# Placa_Base.net
KiCad netlist of a schematic drawn in Altium Designer
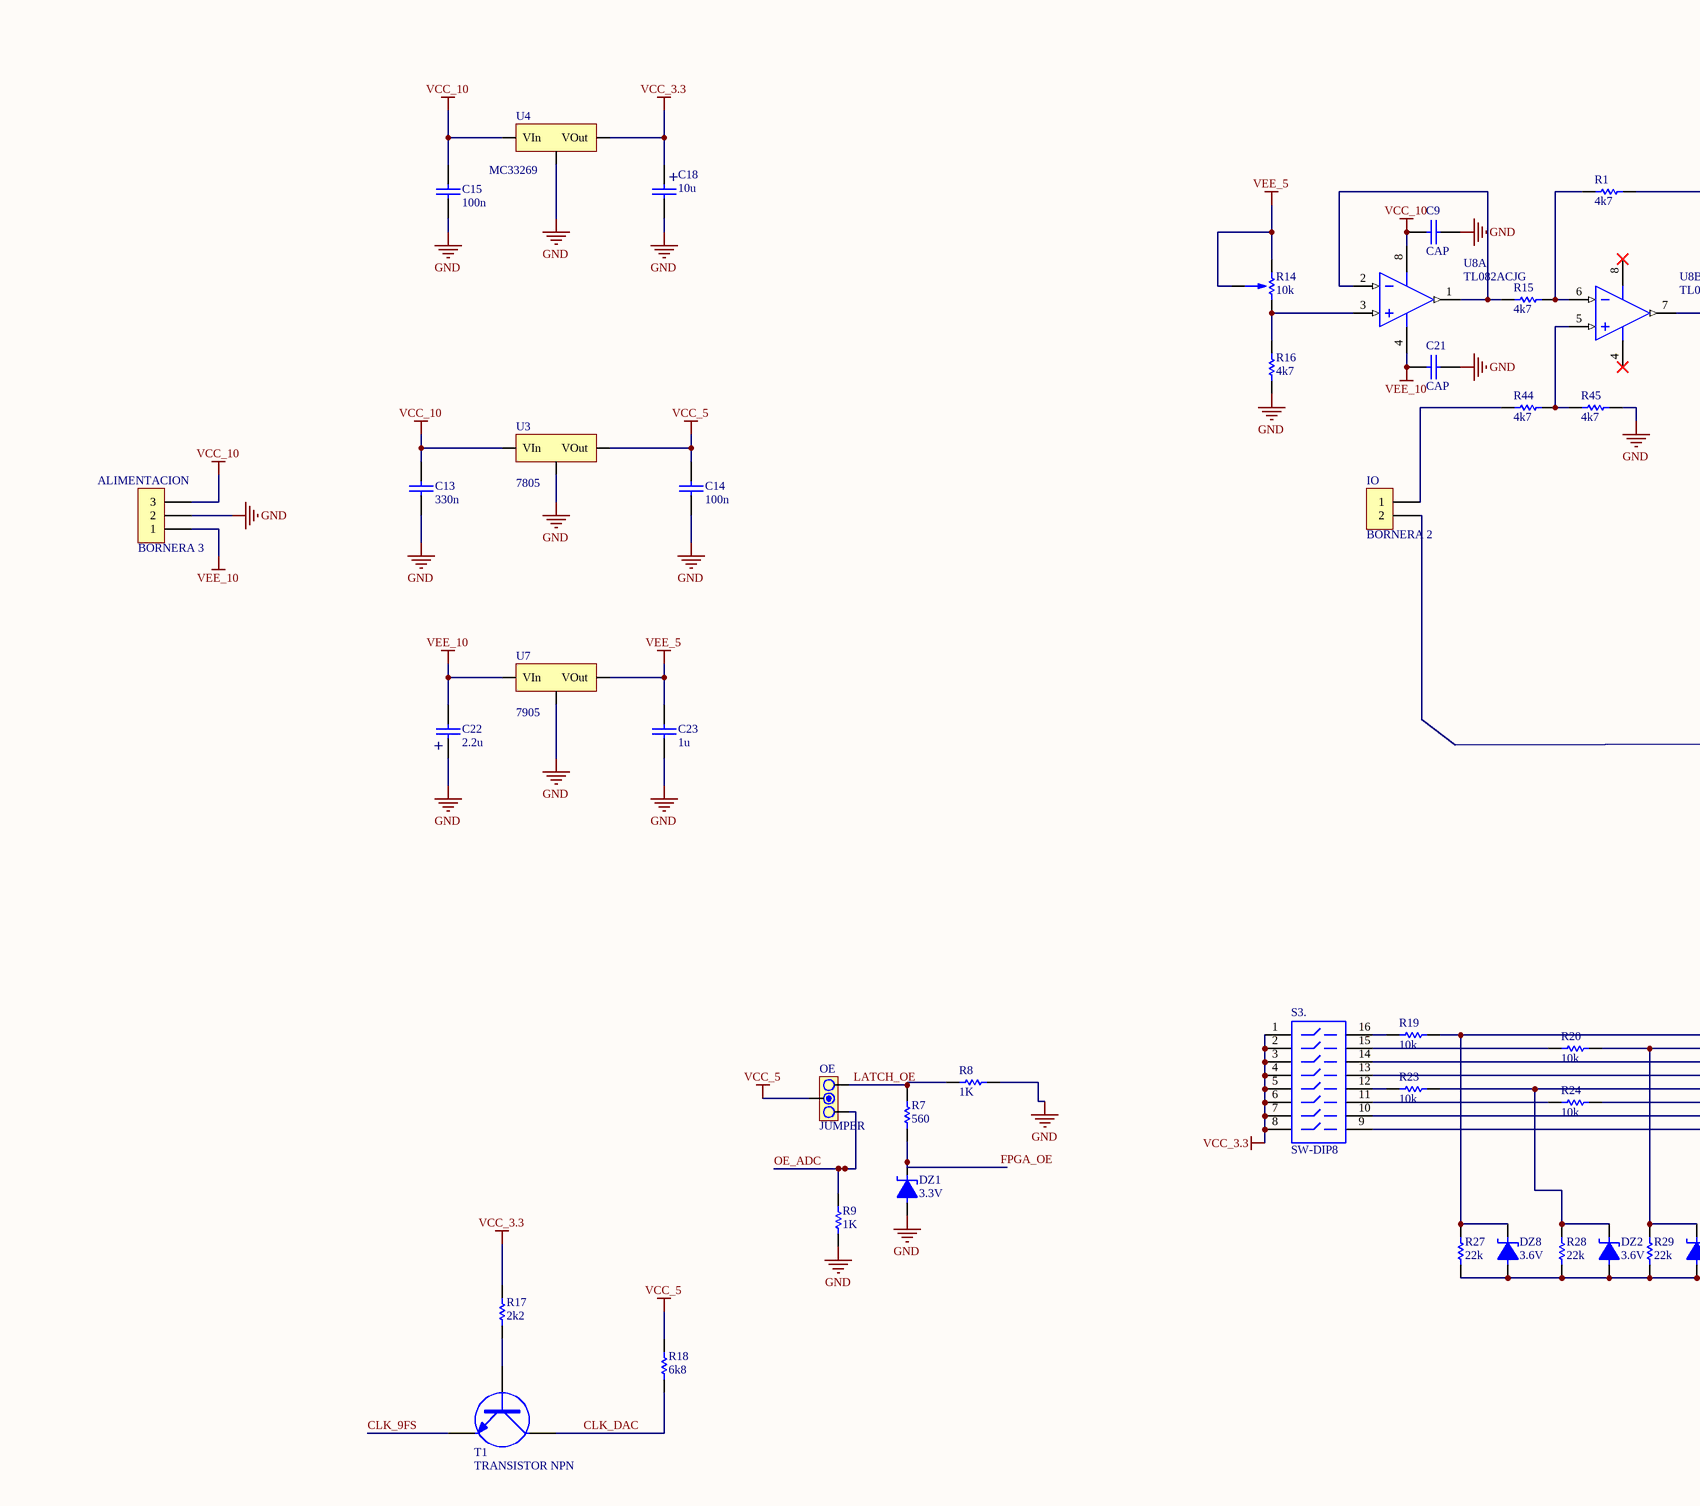
[diagram p0: Placa_Base.SchDoc, top left]
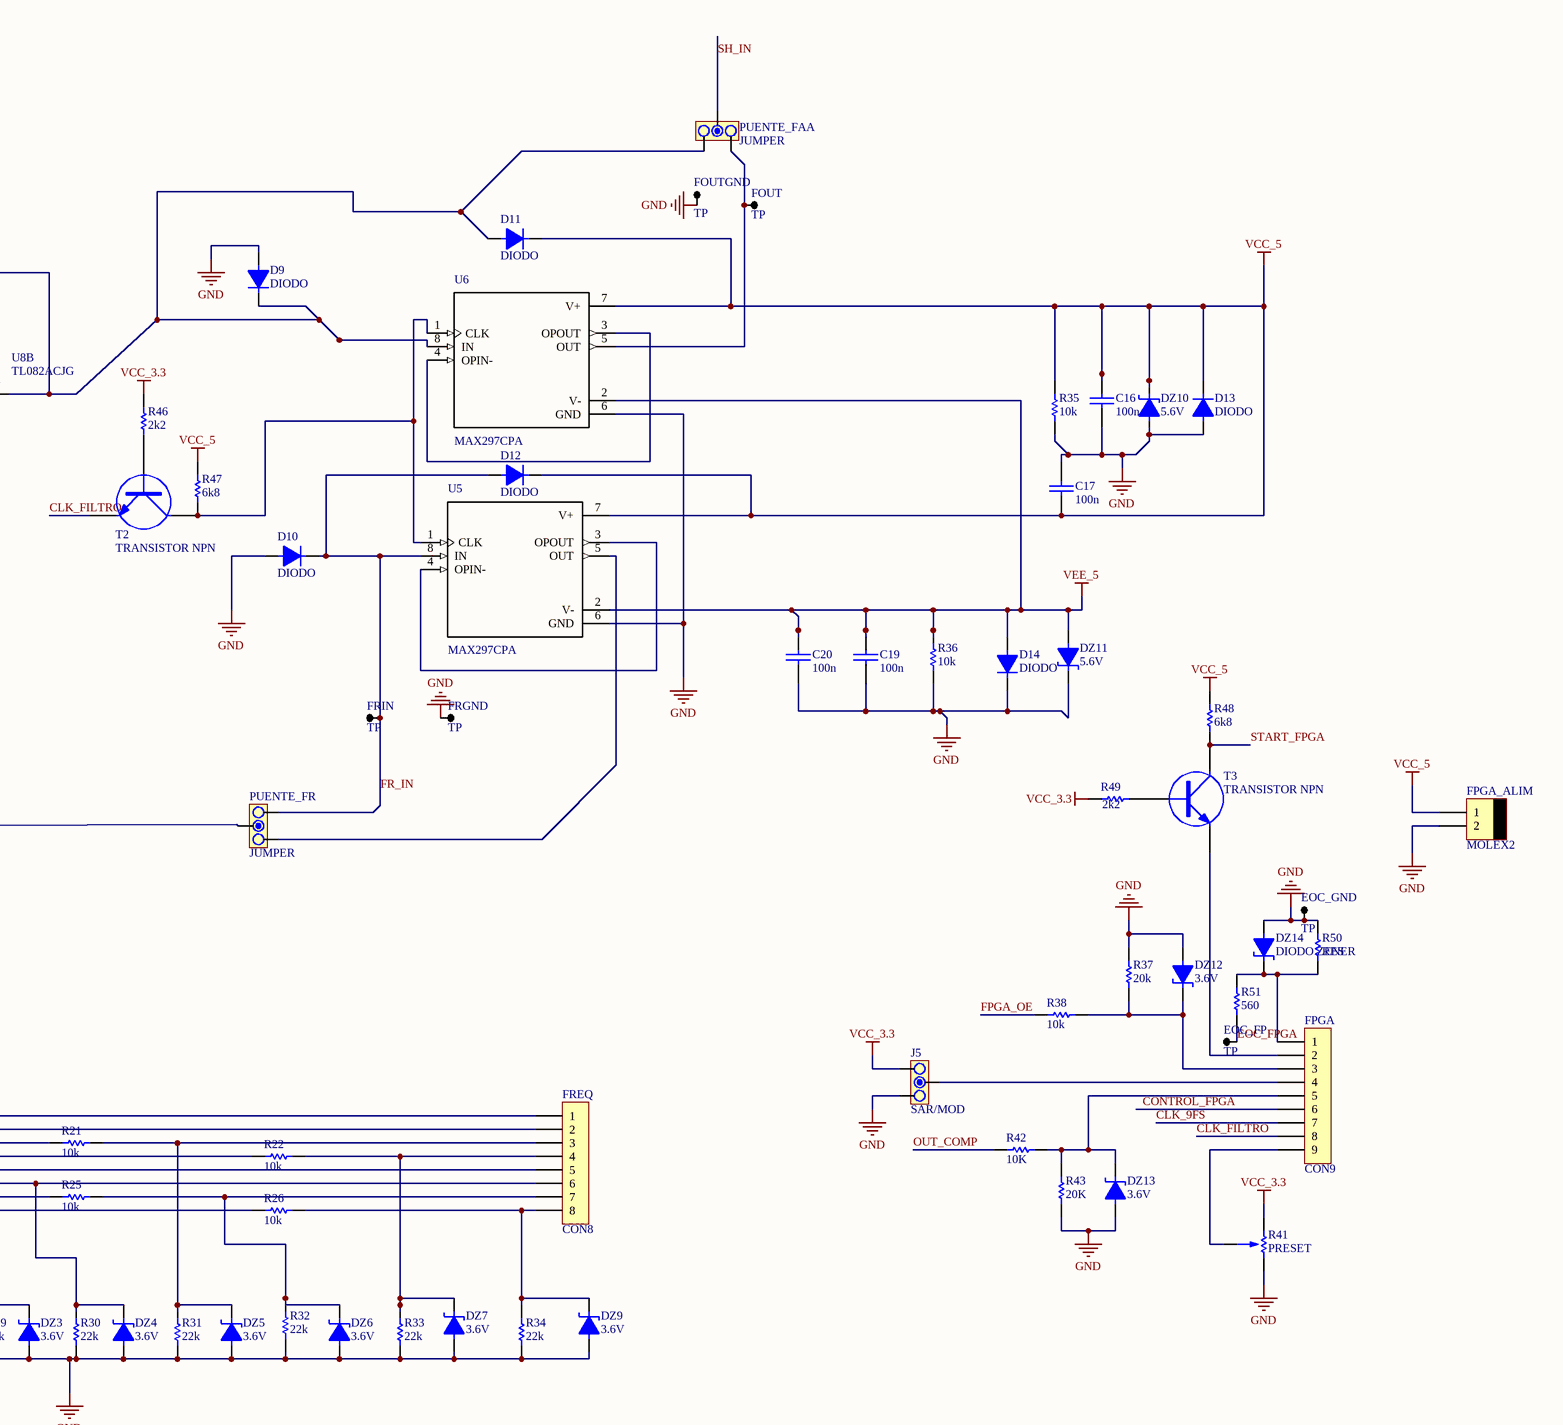
[diagram p1: Placa_Base.SchDoc, top right]
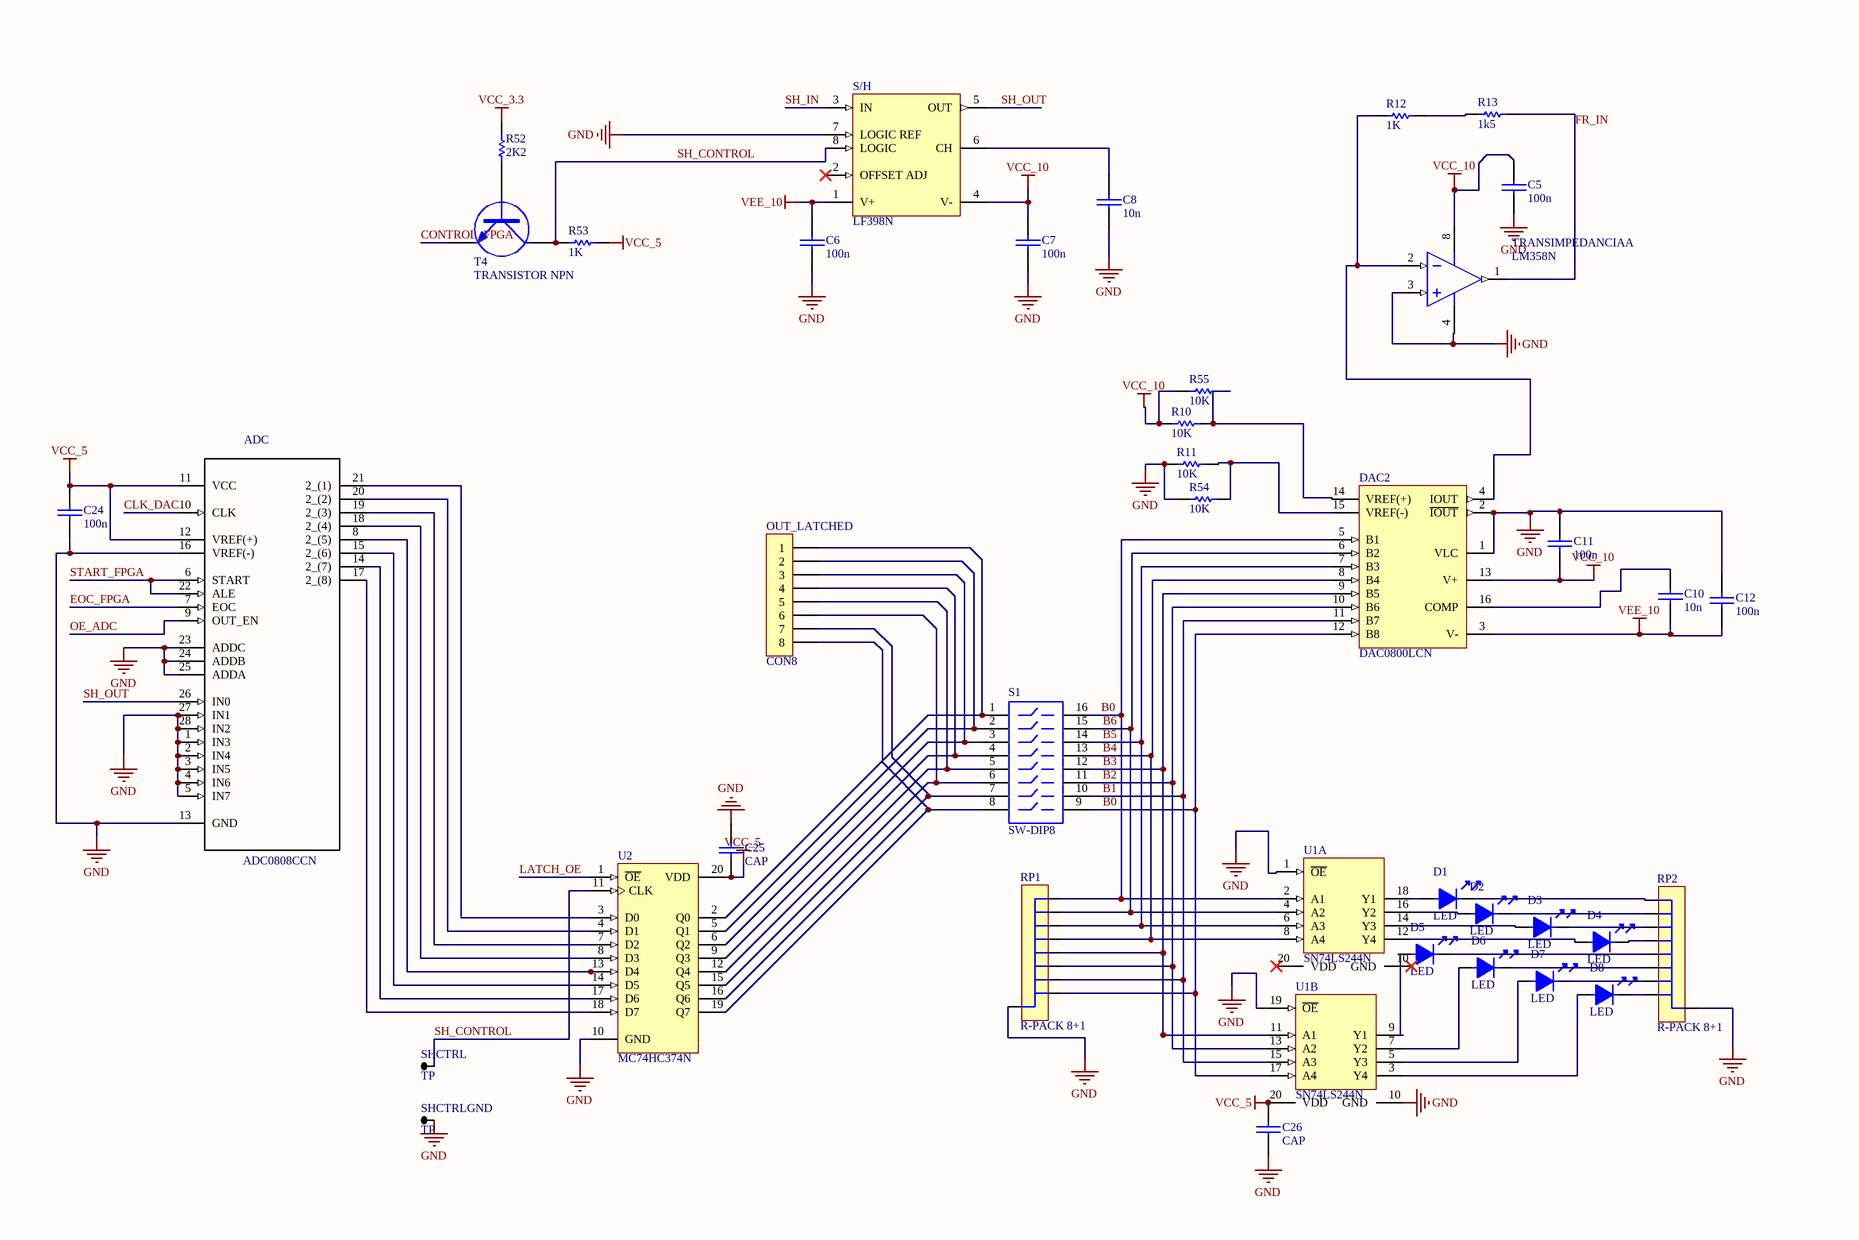
[diagram p2: Placa_Base.SchDoc, bottom left]
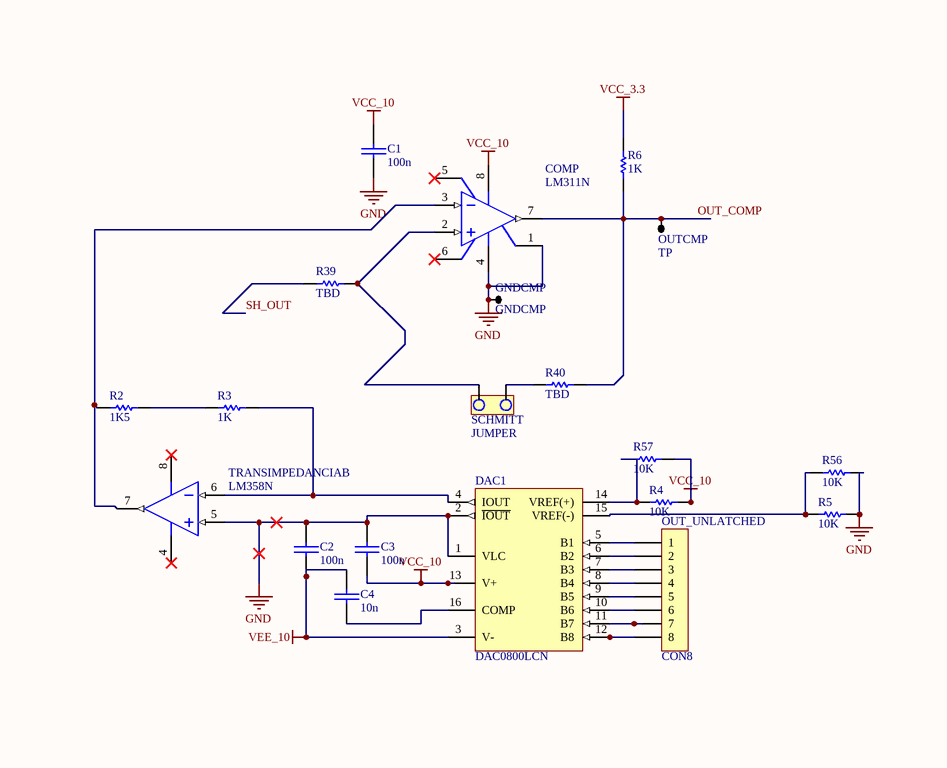
[diagram p3: Placa_Base.SchDoc, bottom right]

(export (version "E")
  (design (tool "Eeschema 10.0.6"))
  (components
    (comp (ref "ADC")
      (value "ADC0808CCN")
      (footprint "DIP28")
      (description "28 pin 8-bit Microprocessor Compatible A/D Converters With 8-Channel Multiplexer 13 per tube")
      (fields (field (name "MF") "Texas Instruments"))
      (libsource (lib "ADC0808CCN") (part "ADC0808CCN"))
    )
    (comp (ref "ALIMENTACION")
      (value "BORNERA 3")
      (footprint "BORNERA3")
      (libsource (lib "LIBEBAL") (part "BORNERA 3"))
    )
    (comp (ref "C1") (value "100n") (footprint "CAP200") (libsource (lib "LIBEBAL") (part "CAP")))
    (comp (ref "C2") (value "100n") (footprint "CAP200") (libsource (lib "LIBEBAL") (part "CAP")))
    (comp (ref "C3") (value "100n") (footprint "CAP200") (libsource (lib "LIBEBAL") (part "CAP")))
    (comp (ref "C4") (value "10n") (footprint "CAP200") (libsource (lib "LIBEBAL") (part "CAP")))
    (comp (ref "C5") (value "100n") (footprint "CAP200") (libsource (lib "LIBEBAL") (part "CAP")))
    (comp (ref "C6") (value "100n") (footprint "CAP200") (libsource (lib "LIBEBAL") (part "CAP")))
    (comp (ref "C7") (value "100n") (footprint "CAP200") (libsource (lib "LIBEBAL") (part "CAP")))
    (comp (ref "C8") (value "10n") (footprint "CAP200") (libsource (lib "LIBEBAL") (part "CAP")))
    (comp (ref "C9") (value "CAP") (footprint "CAP200") (libsource (lib "LIBEBAL") (part "CAP")))
    (comp (ref "C10") (value "10n") (footprint "CAP200") (libsource (lib "LIBEBAL") (part "CAP")))
    (comp (ref "C11") (value "100n") (footprint "CAP200") (libsource (lib "LIBEBAL") (part "CAP")))
    (comp (ref "C12") (value "100n") (footprint "CAP200") (libsource (lib "LIBEBAL") (part "CAP")))
    (comp (ref "C13") (value "330n") (footprint "CAP200") (libsource (lib "LIBEBAL") (part "CAP")))
    (comp (ref "C14") (value "100n") (footprint "CAP200") (libsource (lib "LIBEBAL") (part "CAP")))
    (comp (ref "C15") (value "100n") (footprint "CAP200") (libsource (lib "LIBEBAL") (part "CAP")))
    (comp (ref "C16") (value "100n") (footprint "CAP200") (libsource (lib "LIBEBAL") (part "CAP")))
    (comp (ref "C17") (value "100n") (footprint "CAP200") (libsource (lib "LIBEBAL") (part "CAP")))
    (comp (ref "C18") (value "10u") (footprint "CAP100RP") (libsource (lib "LIBEBAL") (part "CAPPOL")))
    (comp (ref "C19") (value "100n") (footprint "CAP200") (libsource (lib "LIBEBAL") (part "CAP")))
    (comp (ref "C20") (value "100n") (footprint "CAP200") (libsource (lib "LIBEBAL") (part "CAP")))
    (comp (ref "C21") (value "CAP") (footprint "CAP200") (libsource (lib "LIBEBAL") (part "CAP")))
    (comp (ref "C22") (value "2.2u") (footprint "CAP100RP") (libsource (lib "LIBEBAL") (part "CAPPOL")))
    (comp (ref "C23") (value "1u") (footprint "CAP200") (libsource (lib "LIBEBAL") (part "CAP")))
    (comp (ref "C24") (value "100n") (footprint "CAP200") (libsource (lib "LIBEBAL") (part "CAP")))
    (comp (ref "C25") (value "CAP") (footprint "CAP200") (libsource (lib "LIBEBAL") (part "CAP")))
    (comp (ref "C26") (value "CAP") (footprint "CAP200") (libsource (lib "LIBEBAL") (part "CAP")))
    (comp (ref "COMP")
      (value "LM311N")
      (footprint "N08E")
      (description "Voltage Comparator, 8-pin MDIP")
      (fields
        (field (name "MANUFACTURER") "National Semiconductor")
        (field (name "PUBLISHER") "Altium Limited")
      )
      (libsource (lib "NSC Amplifier") (part "LM311N"))
    )
    (comp (ref "D1") (value "LED") (footprint "LED3") (libsource (lib "LIBEBAL") (part "LED")))
    (comp (ref "D2") (value "LED") (footprint "LED3") (libsource (lib "LIBEBAL") (part "LED")))
    (comp (ref "D3") (value "LED") (footprint "LED3") (libsource (lib "LIBEBAL") (part "LED")))
    (comp (ref "D4") (value "LED") (footprint "LED3") (libsource (lib "LIBEBAL") (part "LED")))
    (comp (ref "D5") (value "LED") (footprint "LED3") (libsource (lib "LIBEBAL") (part "LED")))
    (comp (ref "D6") (value "LED") (footprint "LED3") (libsource (lib "LIBEBAL") (part "LED")))
    (comp (ref "D7") (value "LED") (footprint "LED3") (libsource (lib "LIBEBAL") (part "LED")))
    (comp (ref "D8") (value "LED") (footprint "LED3") (libsource (lib "LIBEBAL") (part "LED")))
    (comp (ref "D9") (value "DIODO") (footprint "DO41") (libsource (lib "LIBEBAL") (part "DIODO")))
    (comp (ref "D10") (value "DIODO") (footprint "DO41") (libsource (lib "LIBEBAL") (part "DIODO")))
    (comp (ref "D11") (value "DIODO") (footprint "DO41") (libsource (lib "LIBEBAL") (part "DIODO")))
    (comp (ref "D12") (value "DIODO") (footprint "DO41") (libsource (lib "LIBEBAL") (part "DIODO")))
    (comp (ref "D13") (value "DIODO") (footprint "DO41") (libsource (lib "LIBEBAL") (part "DIODO")))
    (comp (ref "D14") (value "DIODO") (footprint "DO41") (libsource (lib "LIBEBAL") (part "DIODO")))
    (comp (ref "DAC1")
      (value "DAC0800LCN")
      (footprint "N16E")
      (description "8-Bit D/A Converter, 16-pin MDIP")
      (fields
        (field (name "MANUFACTURER") "National Semiconductor")
        (field (name "PUBLISHER") "Altium Limited")
      )
      (libsource (lib "NSC DAC") (part "DAC0800LCN"))
    )
    (comp (ref "DAC2")
      (value "DAC0800LCN")
      (footprint "N16E")
      (description "8-Bit D/A Converter, 16-pin MDIP")
      (fields
        (field (name "MANUFACTURER") "National Semiconductor")
        (field (name "PUBLISHER") "Altium Limited")
      )
      (libsource (lib "") (part "DAC0800LCN_1"))
    )
    (comp (ref "DZ1") (value "3.3V") (footprint "DO41") (libsource (lib "LIBEBAL") (part "DIODO ZENER")))
    (comp (ref "DZ2") (value "3.6V") (footprint "DO41") (libsource (lib "LIBEBAL") (part "DIODO ZENER")))
    (comp (ref "DZ3") (value "3.6V") (footprint "DO41") (libsource (lib "LIBEBAL") (part "DIODO ZENER")))
    (comp (ref "DZ4") (value "3.6V") (footprint "DO41") (libsource (lib "LIBEBAL") (part "DIODO ZENER")))
    (comp (ref "DZ5") (value "3.6V") (footprint "DO41") (libsource (lib "LIBEBAL") (part "DIODO ZENER")))
    (comp (ref "DZ6") (value "3.6V") (footprint "DO41") (libsource (lib "LIBEBAL") (part "DIODO ZENER")))
    (comp (ref "DZ7") (value "3.6V") (footprint "DO41") (libsource (lib "LIBEBAL") (part "DIODO ZENER")))
    (comp (ref "DZ8") (value "3.6V") (footprint "DO41") (libsource (lib "LIBEBAL") (part "DIODO ZENER")))
    (comp (ref "DZ9") (value "3.6V") (footprint "DO41") (libsource (lib "LIBEBAL") (part "DIODO ZENER")))
    (comp (ref "DZ10") (value "5.6V") (footprint "DO41") (libsource (lib "LIBEBAL") (part "DIODO ZENER")))
    (comp (ref "DZ11") (value "5.6V") (footprint "DO41") (libsource (lib "LIBEBAL") (part "DIODO ZENER")))
    (comp (ref "DZ12") (value "3.6V") (footprint "DO41") (libsource (lib "LIBEBAL") (part "DIODO ZENER")))
    (comp (ref "DZ13") (value "3.6V") (footprint "DO41") (libsource (lib "LIBEBAL") (part "DIODO ZENER")))
    (comp (ref "DZ14")
      (value "DIODO ZENER")
      (footprint "DO41")
      (libsource (lib "LIBEBAL") (part "DIODO ZENER"))
    )
    (comp (ref "EOC_FP") (value "TP") (footprint "TPTH") (libsource (lib "LIBEBAL") (part "TP")))
    (comp (ref "EOC_GND") (value "TP") (footprint "TPTH") (libsource (lib "LIBEBAL") (part "TP")))
    (comp (ref "FOUT") (value "TP") (footprint "TPTH") (libsource (lib "LIBEBAL") (part "TP")))
    (comp (ref "FOUTGND") (value "TP") (footprint "TPTH") (libsource (lib "LIBEBAL") (part "TP")))
    (comp (ref "FPGA") (value "CON9") (footprint "SIP9") (libsource (lib "LIBEBAL") (part "CON9")))
    (comp (ref "FPGA_ALIM") (value "MOLEX2") (footprint "MOLEX2") (libsource (lib "LIBEBAL") (part "MOLEX2")))
    (comp (ref "FREQ") (value "CON8") (footprint "SIP8") (libsource (lib "LIBEBAL") (part "CON8")))
    (comp (ref "FRGND") (value "TP") (footprint "TPTH") (libsource (lib "LIBEBAL") (part "TP")))
    (comp (ref "FRIN") (value "TP") (footprint "TPTH") (libsource (lib "LIBEBAL") (part "TP")))
    (comp (ref "GNDCMP") (value "GNDCMP") (footprint "TPTH") (libsource (lib "LIBEBAL") (part "TP")))
    (comp (ref "IO")
      (value "BORNERA 2")
      (footprint "BORNERA2")
      (libsource (lib "LIBEBAL") (part "BORNERA 2"))
    )
    (comp (ref "J5") (value "SAR/MOD") (footprint "JUMPER3") (libsource (lib "") (part "JUMPER3_1")))
    (comp (ref "OE") (value "JUMPER") (footprint "JUMPER3") (libsource (lib "") (part "JUMPER3_2")))
    (comp (ref "OUTCMP") (value "TP") (footprint "TPTH") (libsource (lib "LIBEBAL") (part "TP")))
    (comp (ref "OUT_LATCHED") (value "CON8") (footprint "SIP8") (libsource (lib "") (part "CON8_1")))
    (comp (ref "OUT_UNLATCHED") (value "CON8") (footprint "SIP8") (libsource (lib "LIBEBAL") (part "CON8")))
    (comp (ref "PUENTE_FAA") (value "JUMPER") (footprint "JUMPER3") (libsource (lib "") (part "JUMPER3_3")))
    (comp (ref "PUENTE_FR")
      (value "JUMPER")
      (footprint "JUMPER3")
      (libsource (lib "LIBEBAL") (part "JUMPER3"))
    )
    (comp (ref "R1") (value "4k7") (footprint "RES400") (libsource (lib "LIBEBAL") (part "RES")))
    (comp (ref "R2") (value "1K5") (footprint "RES400") (libsource (lib "LIBEBAL") (part "RES")))
    (comp (ref "R3") (value "1K") (footprint "RES400") (libsource (lib "LIBEBAL") (part "RES")))
    (comp (ref "R4") (value "10K") (footprint "RES400") (libsource (lib "LIBEBAL") (part "RES")))
    (comp (ref "R5") (value "10K") (footprint "RES400") (libsource (lib "LIBEBAL") (part "RES")))
    (comp (ref "R6") (value "1K") (footprint "RES400") (libsource (lib "LIBEBAL") (part "RES")))
    (comp (ref "R7") (value "560") (footprint "RES400") (libsource (lib "LIBEBAL") (part "RES")))
    (comp (ref "R8") (value "1K") (footprint "RES400") (libsource (lib "LIBEBAL") (part "RES")))
    (comp (ref "R9") (value "1K") (footprint "RES400") (libsource (lib "LIBEBAL") (part "RES")))
    (comp (ref "R10") (value "10K") (footprint "RES400") (libsource (lib "LIBEBAL") (part "RES")))
    (comp (ref "R11") (value "10K") (footprint "RES400") (libsource (lib "LIBEBAL") (part "RES")))
    (comp (ref "R12") (value "1K") (footprint "RES400") (libsource (lib "LIBEBAL") (part "RES")))
    (comp (ref "R13") (value "1k5") (footprint "RES400") (libsource (lib "LIBEBAL") (part "RES")))
    (comp (ref "R14") (value "10k") (footprint "PRESET V") (libsource (lib "LIBEBAL") (part "PRESET")))
    (comp (ref "R15") (value "4k7") (footprint "RES400") (libsource (lib "LIBEBAL") (part "RES")))
    (comp (ref "R16") (value "4k7") (footprint "RES400") (libsource (lib "LIBEBAL") (part "RES")))
    (comp (ref "R17") (value "2k2") (footprint "RES400") (libsource (lib "LIBEBAL") (part "RES")))
    (comp (ref "R18") (value "6k8") (footprint "RES400") (libsource (lib "LIBEBAL") (part "RES")))
    (comp (ref "R19") (value "10k") (footprint "RES400") (libsource (lib "LIBEBAL") (part "RES")))
    (comp (ref "R20") (value "10k") (footprint "RES400") (libsource (lib "LIBEBAL") (part "RES")))
    (comp (ref "R21") (value "10k") (footprint "RES400") (libsource (lib "LIBEBAL") (part "RES")))
    (comp (ref "R22") (value "10k") (footprint "RES400") (libsource (lib "LIBEBAL") (part "RES")))
    (comp (ref "R23") (value "10k") (footprint "RES400") (libsource (lib "LIBEBAL") (part "RES")))
    (comp (ref "R24") (value "10k") (footprint "RES400") (libsource (lib "LIBEBAL") (part "RES")))
    (comp (ref "R25") (value "10k") (footprint "RES400") (libsource (lib "LIBEBAL") (part "RES")))
    (comp (ref "R26") (value "10k") (footprint "RES400") (libsource (lib "LIBEBAL") (part "RES")))
    (comp (ref "R27") (value "22k") (footprint "RES400") (libsource (lib "LIBEBAL") (part "RES")))
    (comp (ref "R28") (value "22k") (footprint "RES400") (libsource (lib "LIBEBAL") (part "RES")))
    (comp (ref "R29") (value "22k") (footprint "RES400") (libsource (lib "LIBEBAL") (part "RES")))
    (comp (ref "R30") (value "22k") (footprint "RES400") (libsource (lib "LIBEBAL") (part "RES")))
    (comp (ref "R31") (value "22k") (footprint "RES400") (libsource (lib "LIBEBAL") (part "RES")))
    (comp (ref "R32") (value "22k") (footprint "RES400") (libsource (lib "LIBEBAL") (part "RES")))
    (comp (ref "R33") (value "22k") (footprint "RES400") (libsource (lib "LIBEBAL") (part "RES")))
    (comp (ref "R34") (value "22k") (footprint "RES400") (libsource (lib "LIBEBAL") (part "RES")))
    (comp (ref "R35") (value "10k") (footprint "RES400") (libsource (lib "LIBEBAL") (part "RES")))
    (comp (ref "R36") (value "10k") (footprint "RES400") (libsource (lib "LIBEBAL") (part "RES")))
    (comp (ref "R37") (value "20k") (footprint "RES400") (libsource (lib "LIBEBAL") (part "RES")))
    (comp (ref "R38") (value "10k") (footprint "RES400") (libsource (lib "LIBEBAL") (part "RES")))
    (comp (ref "R39") (value "TBD") (footprint "RES400") (libsource (lib "LIBEBAL") (part "RES")))
    (comp (ref "R40") (value "TBD") (footprint "RES400") (libsource (lib "LIBEBAL") (part "RES")))
    (comp (ref "R41") (value "PRESET") (footprint "PRESET V") (libsource (lib "LIBEBAL") (part "PRESET")))
    (comp (ref "R42") (value "10K") (footprint "RES400") (libsource (lib "LIBEBAL") (part "RES")))
    (comp (ref "R43") (value "20K") (footprint "RES400") (libsource (lib "LIBEBAL") (part "RES")))
    (comp (ref "R44") (value "4k7") (footprint "RES400") (libsource (lib "LIBEBAL") (part "RES")))
    (comp (ref "R45") (value "4k7") (footprint "RES400") (libsource (lib "LIBEBAL") (part "RES")))
    (comp (ref "R46") (value "2k2") (footprint "RES400") (libsource (lib "LIBEBAL") (part "RES")))
    (comp (ref "R47") (value "6k8") (footprint "RES400") (libsource (lib "LIBEBAL") (part "RES")))
    (comp (ref "R48") (value "6k8") (footprint "RES400") (libsource (lib "LIBEBAL") (part "RES")))
    (comp (ref "R49") (value "2k2") (footprint "RES400") (libsource (lib "LIBEBAL") (part "RES")))
    (comp (ref "R50") (value "RES") (footprint "RES400") (libsource (lib "LIBEBAL") (part "RES")))
    (comp (ref "R51") (value "560") (footprint "RES400") (libsource (lib "LIBEBAL") (part "RES")))
    (comp (ref "R52") (value "2K2") (footprint "RES400") (libsource (lib "LIBEBAL") (part "RES")))
    (comp (ref "R53") (value "1K") (footprint "RES400") (libsource (lib "LIBEBAL") (part "RES")))
    (comp (ref "R54") (value "10K") (footprint "RES400") (libsource (lib "LIBEBAL") (part "RES")))
    (comp (ref "R55") (value "10K") (footprint "RES400") (libsource (lib "LIBEBAL") (part "RES")))
    (comp (ref "R56") (value "10K") (footprint "RES400") (libsource (lib "LIBEBAL") (part "RES")))
    (comp (ref "R57") (value "10K") (footprint "RES400") (libsource (lib "LIBEBAL") (part "RES")))
    (comp (ref "RP1")
      (value "R-PACK 8+1")
      (footprint "RESNET8+1")
      (libsource (lib "LIBEBAL") (part "R-PACK 8+1"))
    )
    (comp (ref "RP2") (value "R-PACK 8+1") (footprint "RESNET8+1") (libsource (lib "") (part "R-PACK 8+1_1")))
    (comp (ref "S/H")
      (value "LF398N")
      (footprint "N08E")
      (description "Monolithic Sample and Hold Circuits, 8-pin MDIP")
      (fields
        (field (name "MANUFACTURER") "National Semiconductor")
        (field (name "PUBLISHER") "Altium Limited")
      )
      (libsource (lib "NSC Analog") (part "LF398N"))
    )
    (comp (ref "S1")
      (value "SW-DIP8")
      (footprint "DIP-16-KEY")
      (description "4009 Series DIP Switch, Raised actuator")
      (fields (field (name "PUBLISHER") "Altium Limited"))
      (libsource (lib "Miscellaneous Devices") (part "SW-DIP8"))
    )
    (comp (ref "S3.")
      (value "SW-DIP8")
      (footprint "DIP-16-KEY")
      (description "4009 Series DIP Switch, Raised actuator")
      (fields (field (name "PUBLISHER") "Altium Limited"))
      (libsource (lib "Miscellaneous Devices") (part "SW-DIP8"))
    )
    (comp (ref "SCHMITT") (value "JUMPER") (footprint "JUMPER2") (libsource (lib "LIBEBAL") (part "JUMPER")))
    (comp (ref "SHCTRL") (value "TP") (footprint "TPTH") (libsource (lib "LIBEBAL") (part "TP")))
    (comp (ref "SHCTRLGND") (value "TP") (footprint "TPTH") (libsource (lib "LIBEBAL") (part "TP")))
    (comp (ref "T1")
      (value "TRANSISTOR NPN")
      (footprint "TO92")
      (libsource (lib "LIBEBAL") (part "TRANSISTOR NPN"))
    )
    (comp (ref "T2")
      (value "TRANSISTOR NPN")
      (footprint "TO92")
      (libsource (lib "LIBEBAL") (part "TRANSISTOR NPN"))
    )
    (comp (ref "T3")
      (value "TRANSISTOR NPN")
      (footprint "TO92")
      (libsource (lib "LIBEBAL") (part "TRANSISTOR NPN"))
    )
    (comp (ref "T4")
      (value "TRANSISTOR NPN")
      (footprint "TO92")
      (libsource (lib "LIBEBAL") (part "TRANSISTOR NPN"))
    )
    (comp (ref "TRANSIMPEDANCIA")
      (value "LM358N")
      (footprint "N08E")
      (description "Low Power Dual Operational Amplifier, 8-pin MDIP")
      (fields
        (field (name "MANUFACTURER") "National Semiconductor")
        (field (name "PUBLISHER") "Altium Limited")
      )
      (libsource (lib "NSC Amplifier") (part "LM358N"))
    )
    (comp (ref "U1")
      (value "SN74LS244N")
      (footprint "738-03")
      (description "Octal Buffer/Line Driver with 3-State Outputs")
      (fields (field (name "PUBLISHER") "Altium Limited"))
      (libsource (lib "ON Semi Logic Buffer Line Driver") (part "SN74LS244N"))
    )
    (comp (ref "U2")
      (value "MC74HC374N")
      (footprint "738-03")
      (description "Octal 3-State Non-Inverting D-Type Flip-Flop")
      (fields (field (name "PUBLISHER") "Altium Limited"))
      (libsource (lib "Motorola Logic Flip-Flop") (part "MC74HC374N"))
    )
    (comp (ref "U3")
      (value "7805")
      (footprint "TO-220 V")
      (description "REGULDOR POSITIVO")
      (libsource (lib "LIBEBAL") (part "78XX"))
    )
    (comp (ref "U4")
      (value "MC33269")
      (footprint "TO-220 V")
      (description "REGULDOR POSITIVO")
      (libsource (lib "LIBEBAL") (part "78XX"))
    )
    (comp (ref "U5")
      (value "MAX297CPA")
      (footprint "DIP8")
      (description "Active Filter Single SW-CAP Low Pass 8th Order 50kHz 8-Pin PDIP N")
      (fields (field (name "MF") "Maxim Integrated") (field (name "MP") "MAX297CPA+"))
      (libsource (lib "MAX297CPA") (part "MAX297CPA"))
    )
    (comp (ref "U6")
      (value "MAX297CPA")
      (footprint "DIP8")
      (description "Active Filter Single SW-CAP Low Pass 8th Order 50kHz 8-Pin PDIP N")
      (fields (field (name "MF") "Maxim Integrated") (field (name "MP") "MAX297CPA+"))
      (libsource (lib "MAX297CPA") (part "MAX297CPA"))
    )
    (comp (ref "U7")
      (value "7905")
      (footprint "TO-220 V")
      (description "REGULADOR NEGATIVO")
      (libsource (lib "LIBEBAL") (part "79XX"))
    )
    (comp (ref "U8")
      (value "TL082ACJG")
      (footprint "693-02")
      (description "JFET-Input Operational Amplifier")
      (fields (field (name "PUBLISHER") "Altium Limited"))
      (libsource (lib "Motorola Amplifier Operational Amplifier") (part "TL082ACJG"))
    )
  )
  (nets
    (net (code "1") (name "/B0") (class "Default")
      (node (ref "DAC2") (pin "12") (pinfunction "B8_12") (pintype "input"))
      (node (ref "DAC2") (pin "5") (pinfunction "B1_5") (pintype "input"))
      (node (ref "RP1") (pin "2") (pinfunction "2_2") (pintype "passive"))
      (node (ref "RP1") (pin "9") (pinfunction "9_9") (pintype "passive"))
      (node (ref "S1") (pin "16") (pinfunction "16_16") (pintype "passive"))
      (node (ref "S1") (pin "9") (pinfunction "9_9") (pintype "passive"))
      (node (ref "U1") (pin "17") (pinfunction "A4_17") (pintype "input"))
      (node (ref "U1") (pin "2") (pinfunction "A1_2") (pintype "input"))
    )
    (net (code "2") (name "/B1") (class "Default")
      (node (ref "DAC2") (pin "11") (pinfunction "B7_11") (pintype "input"))
      (node (ref "RP1") (pin "3") (pinfunction "3_3") (pintype "passive"))
      (node (ref "S1") (pin "10") (pinfunction "10_10") (pintype "passive"))
      (node (ref "U1") (pin "15") (pinfunction "A3_15") (pintype "input"))
    )
    (net (code "3") (name "/B2") (class "Default")
      (node (ref "DAC2") (pin "10") (pinfunction "B6_10") (pintype "input"))
      (node (ref "RP1") (pin "4") (pinfunction "4_4") (pintype "passive"))
      (node (ref "S1") (pin "11") (pinfunction "11_11") (pintype "passive"))
      (node (ref "U1") (pin "13") (pinfunction "A2_13") (pintype "input"))
    )
    (net (code "4") (name "/B3") (class "Default")
      (node (ref "DAC2") (pin "9") (pinfunction "B5_9") (pintype "input"))
      (node (ref "RP1") (pin "5") (pinfunction "5_5") (pintype "passive"))
      (node (ref "S1") (pin "12") (pinfunction "12_12") (pintype "passive"))
      (node (ref "U1") (pin "11") (pinfunction "A1_11") (pintype "input"))
    )
    (net (code "5") (name "/B4") (class "Default")
      (node (ref "DAC2") (pin "8") (pinfunction "B4_8") (pintype "input"))
      (node (ref "RP1") (pin "6") (pinfunction "6_6") (pintype "passive"))
      (node (ref "S1") (pin "13") (pinfunction "13_13") (pintype "passive"))
      (node (ref "U1") (pin "8") (pinfunction "A4_8") (pintype "input"))
    )
    (net (code "6") (name "/B5") (class "Default")
      (node (ref "DAC2") (pin "7") (pinfunction "B3_7") (pintype "input"))
      (node (ref "RP1") (pin "7") (pinfunction "7_7") (pintype "passive"))
      (node (ref "S1") (pin "14") (pinfunction "14_14") (pintype "passive"))
      (node (ref "U1") (pin "6") (pinfunction "A3_6") (pintype "input"))
    )
    (net (code "7") (name "/B6") (class "Default")
      (node (ref "DAC2") (pin "6") (pinfunction "B2_6") (pintype "input"))
      (node (ref "RP1") (pin "8") (pinfunction "8_8") (pintype "passive"))
      (node (ref "S1") (pin "15") (pinfunction "15_15") (pintype "passive"))
      (node (ref "U1") (pin "4") (pinfunction "A2_4") (pintype "input"))
    )
    (net (code "8") (name "/CLK_9FS") (class "Default")
      (node (ref "FPGA") (pin "7") (pinfunction "7_7") (pintype "passive"))
      (node (ref "T1") (pin "3") (pinfunction "E_3") (pintype "passive"))
    )
    (net (code "9") (name "/CLK_DAC") (class "Default")
      (node (ref "ADC") (pin "10") (pinfunction "CLK_10") (pintype "input"))
      (node (ref "R18") (pin "1") (pinfunction "1_1") (pintype "passive"))
      (node (ref "T1") (pin "2") (pinfunction "C_2") (pintype "passive"))
    )
    (net (code "10") (name "/CLK_FILTRO") (class "Default")
      (node (ref "FPGA") (pin "8") (pinfunction "8_8") (pintype "passive"))
      (node (ref "T2") (pin "3") (pinfunction "E_3") (pintype "passive"))
    )
    (net (code "11") (name "/CONTROL_FPGA") (class "Default")
      (node (ref "FPGA") (pin "6") (pinfunction "6_6") (pintype "passive"))
      (node (ref "T4") (pin "3") (pinfunction "E_3") (pintype "passive"))
    )
    (net (code "12") (name "/EOC_FPGA") (class "Default")
      (node (ref "ADC") (pin "7") (pinfunction "EOC_7") (pintype "input"))
      (node (ref "EOC_FP") (pin "1") (pinfunction "1_1") (pintype "passive"))
      (node (ref "R51") (pin "1") (pinfunction "1_1") (pintype "passive"))
    )
    (net (code "13") (name "/FPGA_OE") (class "Default")
      (node (ref "DZ1") (pin "2") (pinfunction "2_2") (pintype "passive"))
      (node (ref "R38") (pin "1") (pinfunction "1_1") (pintype "passive"))
      (node (ref "R7") (pin "1") (pinfunction "1_1") (pintype "passive"))
    )
    (net (code "14") (name "/FR_IN") (class "Default")
      (node (ref "D10") (pin "2") (pinfunction "2_2") (pintype "passive"))
      (node (ref "D12") (pin "1") (pinfunction "1_1") (pintype "passive"))
      (node (ref "FRIN") (pin "1") (pinfunction "1_1") (pintype "passive"))
      (node (ref "PUENTE_FR") (pin "1") (pinfunction "1_1") (pintype "passive"))
      (node (ref "R13") (pin "2") (pinfunction "2_2") (pintype "passive"))
      (node (ref "TRANSIMPEDANCIA") (pin "1") (pinfunction "OUTA_1") (pintype "output"))
      (node (ref "U5") (pin "8") (pinfunction "IN_8") (pintype "input"))
    )
    (net (code "15") (name "/LATCH_OE") (class "Default")
      (node (ref "OE") (pin "3") (pinfunction "3_3") (pintype "passive"))
      (node (ref "R7") (pin "2") (pinfunction "2_2") (pintype "passive"))
      (node (ref "R8") (pin "2") (pinfunction "2_2") (pintype "passive"))
      (node (ref "U2") (pin "1") (pinfunction "~{OE}_1") (pintype "input"))
    )
    (net (code "16") (name "/OE_ADC") (class "Default")
      (node (ref "ADC") (pin "9") (pinfunction "OUT_EN_9") (pintype "input"))
      (node (ref "OE") (pin "1") (pinfunction "1_1") (pintype "passive"))
      (node (ref "R9") (pin "2") (pinfunction "2_2") (pintype "passive"))
    )
    (net (code "17") (name "/OUT_COMP") (class "Default")
      (node (ref "COMP") (pin "7") (pinfunction "OUT_7") (pintype "output"))
      (node (ref "OUTCMP") (pin "1") (pinfunction "1_1") (pintype "passive"))
      (node (ref "R40") (pin "2") (pinfunction "2_2") (pintype "passive"))
      (node (ref "R42") (pin "1") (pinfunction "1_1") (pintype "passive"))
      (node (ref "R6") (pin "1") (pinfunction "1_1") (pintype "passive"))
    )
    (net (code "18") (name "/SH_CONTROL") (class "Default")
      (node (ref "R53") (pin "2") (pinfunction "2_2") (pintype "passive"))
      (node (ref "S/H") (pin "8") (pinfunction "LOGIC_8") (pintype "input"))
      (node (ref "SHCTRL") (pin "1") (pinfunction "1_1") (pintype "passive"))
      (node (ref "T4") (pin "2") (pinfunction "C_2") (pintype "passive"))
      (node (ref "U2") (pin "11") (pinfunction "CLK_11") (pintype "input"))
    )
    (net (code "19") (name "/SH_IN") (class "Default")
      (node (ref "PUENTE_FAA") (pin "2") (pinfunction "2_2") (pintype "passive"))
      (node (ref "S/H") (pin "3") (pinfunction "IN_3") (pintype "input"))
    )
    (net (code "20") (name "/SH_OUT") (class "Default")
      (node (ref "ADC") (pin "26") (pinfunction "IN0_26") (pintype "input"))
      (node (ref "R39") (pin "1") (pinfunction "1_1") (pintype "passive"))
      (node (ref "S/H") (pin "5") (pinfunction "OUT_5") (pintype "output"))
    )
    (net (code "21") (name "/START_FPGA") (class "Default")
      (node (ref "ADC") (pin "22") (pinfunction "ALE_22") (pintype "input"))
      (node (ref "ADC") (pin "6") (pinfunction "START_6") (pintype "input"))
      (node (ref "R48") (pin "2") (pinfunction "2_2") (pintype "passive"))
      (node (ref "T3") (pin "2") (pinfunction "C_2") (pintype "passive"))
    )
    (net (code "22") (name "GND") (class "Default")
      (node (ref "ADC") (pin "1") (pinfunction "IN3_1") (pintype "input"))
      (node (ref "ADC") (pin "13") (pinfunction "GND_13") (pintype "passive"))
      (node (ref "ADC") (pin "16") (pinfunction "VREF(-)_16") (pintype "passive"))
      (node (ref "ADC") (pin "2") (pinfunction "IN4_2") (pintype "input"))
      (node (ref "ADC") (pin "23") (pinfunction "ADDC_23") (pintype "passive"))
      (node (ref "ADC") (pin "24") (pinfunction "ADDB_24") (pintype "passive"))
      (node (ref "ADC") (pin "25") (pinfunction "ADDA_25") (pintype "passive"))
      (node (ref "ADC") (pin "27") (pinfunction "IN1_27") (pintype "input"))
      (node (ref "ADC") (pin "28") (pinfunction "IN2_28") (pintype "input"))
      (node (ref "ADC") (pin "3") (pinfunction "IN5_3") (pintype "input"))
      (node (ref "ADC") (pin "4") (pinfunction "IN6_4") (pintype "input"))
      (node (ref "ADC") (pin "5") (pinfunction "IN7_5") (pintype "input"))
      (node (ref "ALIMENTACION") (pin "2") (pinfunction "2_2") (pintype "passive"))
      (node (ref "C1") (pin "2") (pinfunction "2_2") (pintype "passive"))
      (node (ref "C11") (pin "1") (pinfunction "1_1") (pintype "passive"))
      (node (ref "C12") (pin "1") (pinfunction "1_1") (pintype "passive"))
      (node (ref "C13") (pin "2") (pinfunction "2_2") (pintype "passive"))
      (node (ref "C14") (pin "2") (pinfunction "2_2") (pintype "passive"))
      (node (ref "C15") (pin "2") (pinfunction "2_2") (pintype "passive"))
      (node (ref "C16") (pin "2") (pinfunction "2_2") (pintype "passive"))
      (node (ref "C17") (pin "1") (pinfunction "1_1") (pintype "passive"))
      (node (ref "C18") (pin "2") (pinfunction "2_2") (pintype "passive"))
      (node (ref "C19") (pin "2") (pinfunction "2_2") (pintype "passive"))
      (node (ref "C2") (pin "1") (pinfunction "1_1") (pintype "passive"))
      (node (ref "C20") (pin "2") (pinfunction "2_2") (pintype "passive"))
      (node (ref "C21") (pin "2") (pinfunction "2_2") (pintype "passive"))
      (node (ref "C22") (pin "1") (pinfunction "1_1") (pintype "passive"))
      (node (ref "C23") (pin "2") (pinfunction "2_2") (pintype "passive"))
      (node (ref "C24") (pin "2") (pinfunction "2_2") (pintype "passive"))
      (node (ref "C25") (pin "1") (pinfunction "1_1") (pintype "passive"))
      (node (ref "C26") (pin "2") (pinfunction "2_2") (pintype "passive"))
      (node (ref "C3") (pin "1") (pinfunction "1_1") (pintype "passive"))
      (node (ref "C5") (pin "2") (pinfunction "2_2") (pintype "passive"))
      (node (ref "C6") (pin "2") (pinfunction "2_2") (pintype "passive"))
      (node (ref "C7") (pin "2") (pinfunction "2_2") (pintype "passive"))
      (node (ref "C8") (pin "2") (pinfunction "2_2") (pintype "passive"))
      (node (ref "C9") (pin "2") (pinfunction "2_2") (pintype "passive"))
      (node (ref "COMP") (pin "1") (pinfunction "GND_1") (pintype "power_in"))
      (node (ref "COMP") (pin "4") (pinfunction "V-_4") (pintype "power_in"))
      (node (ref "D10") (pin "1") (pinfunction "1_1") (pintype "passive"))
      (node (ref "D13") (pin "1") (pinfunction "1_1") (pintype "passive"))
      (node (ref "D14") (pin "2") (pinfunction "2_2") (pintype "passive"))
      (node (ref "D9") (pin "1") (pinfunction "1_1") (pintype "passive"))
      (node (ref "DAC1") (pin "1") (pinfunction "VLC_1") (pintype "passive"))
      (node (ref "DAC1") (pin "2") (pinfunction "~{IOUT}_2") (pintype "output"))
      (node (ref "DAC2") (pin "1") (pinfunction "VLC_1") (pintype "passive"))
      (node (ref "DAC2") (pin "2") (pinfunction "~{IOUT}_2") (pintype "output"))
      (node (ref "DZ1") (pin "1") (pinfunction "1_1") (pintype "passive"))
      (node (ref "DZ10") (pin "1") (pinfunction "1_1") (pintype "passive"))
      (node (ref "DZ11") (pin "2") (pinfunction "2_2") (pintype "passive"))
      (node (ref "DZ12") (pin "1") (pinfunction "1_1") (pintype "passive"))
      (node (ref "DZ13") (pin "1") (pinfunction "1_1") (pintype "passive"))
      (node (ref "DZ14") (pin "1") (pinfunction "1_1") (pintype "passive"))
      (node (ref "DZ2") (pin "1") (pinfunction "1_1") (pintype "passive"))
      (node (ref "DZ3") (pin "1") (pinfunction "1_1") (pintype "passive"))
      (node (ref "DZ4") (pin "1") (pinfunction "1_1") (pintype "passive"))
      (node (ref "DZ5") (pin "1") (pinfunction "1_1") (pintype "passive"))
      (node (ref "DZ6") (pin "1") (pinfunction "1_1") (pintype "passive"))
      (node (ref "DZ7") (pin "1") (pinfunction "1_1") (pintype "passive"))
      (node (ref "DZ8") (pin "1") (pinfunction "1_1") (pintype "passive"))
      (node (ref "DZ9") (pin "1") (pinfunction "1_1") (pintype "passive"))
      (node (ref "EOC_GND") (pin "1") (pinfunction "1_1") (pintype "passive"))
      (node (ref "FOUTGND") (pin "1") (pinfunction "1_1") (pintype "passive"))
      (node (ref "FPGA_ALIM") (pin "2") (pinfunction "2_2") (pintype "passive"))
      (node (ref "FRGND") (pin "1") (pinfunction "1_1") (pintype "passive"))
      (node (ref "GNDCMP") (pin "1") (pinfunction "1_1") (pintype "passive"))
      (node (ref "J5") (pin "1") (pinfunction "1_1") (pintype "passive"))
      (node (ref "R11") (pin "1") (pinfunction "1_1") (pintype "passive"))
      (node (ref "R16") (pin "2") (pinfunction "2_2") (pintype "passive"))
      (node (ref "R27") (pin "1") (pinfunction "1_1") (pintype "passive"))
      (node (ref "R28") (pin "1") (pinfunction "1_1") (pintype "passive"))
      (node (ref "R29") (pin "1") (pinfunction "1_1") (pintype "passive"))
      (node (ref "R30") (pin "1") (pinfunction "1_1") (pintype "passive"))
      (node (ref "R31") (pin "1") (pinfunction "1_1") (pintype "passive"))
      (node (ref "R32") (pin "1") (pinfunction "1_1") (pintype "passive"))
      (node (ref "R33") (pin "1") (pinfunction "1_1") (pintype "passive"))
      (node (ref "R34") (pin "1") (pinfunction "1_1") (pintype "passive"))
      (node (ref "R35") (pin "1") (pinfunction "1_1") (pintype "passive"))
      (node (ref "R36") (pin "1") (pinfunction "1_1") (pintype "passive"))
      (node (ref "R37") (pin "2") (pinfunction "2_2") (pintype "passive"))
      (node (ref "R41") (pin "1") (pinfunction "1_1") (pintype "passive"))
      (node (ref "R43") (pin "1") (pinfunction "1_1") (pintype "passive"))
      (node (ref "R45") (pin "2") (pinfunction "2_2") (pintype "passive"))
      (node (ref "R5") (pin "2") (pinfunction "2_2") (pintype "passive"))
      (node (ref "R50") (pin "2") (pinfunction "2_2") (pintype "passive"))
      (node (ref "R54") (pin "1") (pinfunction "1_1") (pintype "passive"))
      (node (ref "R56") (pin "2") (pinfunction "2_2") (pintype "passive"))
      (node (ref "R8") (pin "1") (pinfunction "1_1") (pintype "passive"))
      (node (ref "R9") (pin "1") (pinfunction "1_1") (pintype "passive"))
      (node (ref "RP1") (pin "1") (pinfunction "1_1") (pintype "passive"))
      (node (ref "RP2") (pin "1") (pinfunction "1_1") (pintype "passive"))
      (node (ref "S/H") (pin "7") (pinfunction "LOGIC_REF_7") (pintype "input"))
      (node (ref "SHCTRLGND") (pin "1") (pinfunction "1_1") (pintype "passive"))
      (node (ref "TRANSIMPEDANCIA") (pin "3") (pinfunction "INA+_3") (pintype "input"))
      (node (ref "TRANSIMPEDANCIA") (pin "4") (pinfunction "GND_4") (pintype "power_in"))
      (node (ref "TRANSIMPEDANCIA") (pin "5") (pinfunction "INB+_5") (pintype "input"))
      (node (ref "U1") (pin "1") (pinfunction "~{OE}_1") (pintype "input"))
      (node (ref "U1") (pin "10") (pinfunction "GND_10") (pintype "power_in"))
      (node (ref "U1") (pin "19") (pinfunction "~{OE}_19") (pintype "input"))
      (node (ref "U2") (pin "10") (pinfunction "GND_10") (pintype "power_in"))
      (node (ref "U3") (pin "2") (pinfunction "GND_2") (pintype "passive"))
      (node (ref "U4") (pin "2") (pinfunction "GND_2") (pintype "passive"))
      (node (ref "U5") (pin "6") (pinfunction "GND_6") (pintype "power_in"))
      (node (ref "U6") (pin "6") (pinfunction "GND_6") (pintype "power_in"))
      (node (ref "U7") (pin "1") (pinfunction "GND_1") (pintype "passive"))
    )
    (net (code "23") (name "Net-(ADC-2_(1))") (class "Default")
      (node (ref "ADC") (pin "21") (pinfunction "2_(1)_21") (pintype "passive"))
      (node (ref "U2") (pin "3") (pinfunction "D0_3") (pintype "input"))
    )
    (net (code "24") (name "Net-(ADC-2_(2))") (class "Default")
      (node (ref "ADC") (pin "20") (pinfunction "2_(2)_20") (pintype "passive"))
      (node (ref "U2") (pin "4") (pinfunction "D1_4") (pintype "input"))
    )
    (net (code "25") (name "Net-(ADC-2_(3))") (class "Default")
      (node (ref "ADC") (pin "19") (pinfunction "2_(3)_19") (pintype "passive"))
      (node (ref "U2") (pin "7") (pinfunction "D2_7") (pintype "input"))
    )
    (net (code "26") (name "Net-(ADC-2_(4))") (class "Default")
      (node (ref "ADC") (pin "18") (pinfunction "2_(4)_18") (pintype "passive"))
      (node (ref "U2") (pin "8") (pinfunction "D3_8") (pintype "input"))
    )
    (net (code "27") (name "Net-(ADC-2_(5))") (class "Default")
      (node (ref "ADC") (pin "8") (pinfunction "2_(5)_8") (pintype "passive"))
      (node (ref "U2") (pin "13") (pinfunction "D4_13") (pintype "input"))
    )
    (net (code "28") (name "Net-(ADC-2_(6))") (class "Default")
      (node (ref "ADC") (pin "15") (pinfunction "2_(6)_15") (pintype "passive"))
      (node (ref "U2") (pin "14") (pinfunction "D5_14") (pintype "input"))
    )
    (net (code "29") (name "Net-(ADC-2_(7))") (class "Default")
      (node (ref "ADC") (pin "14") (pinfunction "2_(7)_14") (pintype "passive"))
      (node (ref "U2") (pin "17") (pinfunction "D6_17") (pintype "input"))
    )
    (net (code "30") (name "Net-(ADC-2_(8))") (class "Default")
      (node (ref "ADC") (pin "17") (pinfunction "2_(8)_17") (pintype "passive"))
      (node (ref "U2") (pin "18") (pinfunction "D7_18") (pintype "input"))
    )
    (net (code "31") (name "Net-(COMP-IN+)") (class "Default")
      (node (ref "COMP") (pin "2") (pinfunction "IN+_2") (pintype "input"))
      (node (ref "R39") (pin "2") (pinfunction "2_2") (pintype "passive"))
      (node (ref "SCHMITT") (pin "1") (pinfunction "1_1") (pintype "passive"))
    )
    (net (code "32") (name "Net-(COMP-IN-)") (class "Default")
      (node (ref "COMP") (pin "3") (pinfunction "IN-_3") (pintype "input"))
      (node (ref "R2") (pin "1") (pinfunction "1_1") (pintype "passive"))
      (node (ref "TRANSIMPEDANCIA") (pin "7") (pinfunction "OUTB_7") (pintype "output"))
    )
    (net (code "33") (name "Net-(D1-Pad2)") (class "Default")
      (node (ref "D1") (pin "2") (pinfunction "2_2") (pintype "passive"))
      (node (ref "RP2") (pin "9") (pinfunction "9_9") (pintype "passive"))
    )
    (net (code "34") (name "Net-(D2-Pad2)") (class "Default")
      (node (ref "D2") (pin "2") (pinfunction "2_2") (pintype "passive"))
      (node (ref "RP2") (pin "8") (pinfunction "8_8") (pintype "passive"))
    )
    (net (code "35") (name "Net-(D3-Pad2)") (class "Default")
      (node (ref "D3") (pin "2") (pinfunction "2_2") (pintype "passive"))
      (node (ref "RP2") (pin "7") (pinfunction "7_7") (pintype "passive"))
    )
    (net (code "36") (name "Net-(D4-Pad2)") (class "Default")
      (node (ref "D4") (pin "2") (pinfunction "2_2") (pintype "passive"))
      (node (ref "RP2") (pin "6") (pinfunction "6_6") (pintype "passive"))
    )
    (net (code "37") (name "Net-(D5-Pad2)") (class "Default")
      (node (ref "D5") (pin "2") (pinfunction "2_2") (pintype "passive"))
      (node (ref "RP2") (pin "5") (pinfunction "5_5") (pintype "passive"))
    )
    (net (code "38") (name "Net-(D6-Pad2)") (class "Default")
      (node (ref "D6") (pin "2") (pinfunction "2_2") (pintype "passive"))
      (node (ref "RP2") (pin "4") (pinfunction "4_4") (pintype "passive"))
    )
    (net (code "39") (name "Net-(D7-Pad2)") (class "Default")
      (node (ref "D7") (pin "2") (pinfunction "2_2") (pintype "passive"))
      (node (ref "RP2") (pin "3") (pinfunction "3_3") (pintype "passive"))
    )
    (net (code "40") (name "Net-(D8-Pad2)") (class "Default")
      (node (ref "D8") (pin "2") (pinfunction "2_2") (pintype "passive"))
      (node (ref "RP2") (pin "2") (pinfunction "2_2") (pintype "passive"))
    )
    (net (code "41") (name "Net-(DAC1-B1)") (class "Default")
      (node (ref "DAC1") (pin "5") (pinfunction "B1_5") (pintype "input"))
      (node (ref "OUT_UNLATCHED") (pin "1") (pinfunction "1_1") (pintype "passive"))
    )
    (net (code "42") (name "Net-(DAC1-B2)") (class "Default")
      (node (ref "DAC1") (pin "6") (pinfunction "B2_6") (pintype "input"))
      (node (ref "OUT_UNLATCHED") (pin "2") (pinfunction "2_2") (pintype "passive"))
    )
    (net (code "43") (name "Net-(DAC1-B3)") (class "Default")
      (node (ref "DAC1") (pin "7") (pinfunction "B3_7") (pintype "input"))
      (node (ref "OUT_UNLATCHED") (pin "3") (pinfunction "3_3") (pintype "passive"))
    )
    (net (code "44") (name "Net-(DAC1-B4)") (class "Default")
      (node (ref "DAC1") (pin "8") (pinfunction "B4_8") (pintype "input"))
      (node (ref "OUT_UNLATCHED") (pin "4") (pinfunction "4_4") (pintype "passive"))
    )
    (net (code "45") (name "Net-(DAC1-B5)") (class "Default")
      (node (ref "DAC1") (pin "9") (pinfunction "B5_9") (pintype "input"))
      (node (ref "OUT_UNLATCHED") (pin "5") (pinfunction "5_5") (pintype "passive"))
    )
    (net (code "46") (name "Net-(DAC1-B6)") (class "Default")
      (node (ref "DAC1") (pin "10") (pinfunction "B6_10") (pintype "input"))
      (node (ref "OUT_UNLATCHED") (pin "6") (pinfunction "6_6") (pintype "passive"))
    )
    (net (code "47") (name "Net-(DAC1-B7)") (class "Default")
      (node (ref "DAC1") (pin "11") (pinfunction "B7_11") (pintype "input"))
      (node (ref "OUT_UNLATCHED") (pin "7") (pinfunction "7_7") (pintype "passive"))
    )
    (net (code "48") (name "Net-(DAC1-B8)") (class "Default")
      (node (ref "DAC1") (pin "12") (pinfunction "B8_12") (pintype "input"))
      (node (ref "OUT_UNLATCHED") (pin "8") (pinfunction "8_8") (pintype "passive"))
    )
    (net (code "49") (name "Net-(DAC1-COMP)") (class "Default")
      (node (ref "C4") (pin "2") (pinfunction "2_2") (pintype "passive"))
      (node (ref "DAC1") (pin "16") (pinfunction "COMP_16") (pintype "passive"))
    )
    (net (code "50") (name "Net-(DAC1-IOUT)") (class "Default")
      (node (ref "DAC1") (pin "4") (pinfunction "IOUT_4") (pintype "output"))
      (node (ref "R3") (pin "2") (pinfunction "2_2") (pintype "passive"))
      (node (ref "TRANSIMPEDANCIA") (pin "6") (pinfunction "INB-_6") (pintype "input"))
    )
    (net (code "51") (name "Net-(DAC1-VREF(+))") (class "Default")
      (node (ref "DAC1") (pin "14") (pinfunction "VREF(+)_14") (pintype "power_in"))
      (node (ref "R4") (pin "1") (pinfunction "1_1") (pintype "passive"))
      (node (ref "R57") (pin "1") (pinfunction "1_1") (pintype "passive"))
    )
    (net (code "52") (name "Net-(DAC1-VREF(-))") (class "Default")
      (node (ref "DAC1") (pin "15") (pinfunction "VREF(-)_15") (pintype "power_in"))
      (node (ref "R5") (pin "1") (pinfunction "1_1") (pintype "passive"))
      (node (ref "R56") (pin "1") (pinfunction "1_1") (pintype "passive"))
    )
    (net (code "53") (name "Net-(DAC2-COMP)") (class "Default")
      (node (ref "C10") (pin "1") (pinfunction "1_1") (pintype "passive"))
      (node (ref "DAC2") (pin "16") (pinfunction "COMP_16") (pintype "passive"))
    )
    (net (code "54") (name "Net-(DAC2-IOUT)") (class "Default")
      (node (ref "DAC2") (pin "4") (pinfunction "IOUT_4") (pintype "output"))
      (node (ref "R12") (pin "1") (pinfunction "1_1") (pintype "passive"))
      (node (ref "TRANSIMPEDANCIA") (pin "2") (pinfunction "INA-_2") (pintype "input"))
    )
    (net (code "55") (name "Net-(DAC2-VREF(+))") (class "Default")
      (node (ref "DAC2") (pin "14") (pinfunction "VREF(+)_14") (pintype "power_in"))
      (node (ref "R10") (pin "2") (pinfunction "2_2") (pintype "passive"))
      (node (ref "R55") (pin "2") (pinfunction "2_2") (pintype "passive"))
    )
    (net (code "56") (name "Net-(DAC2-VREF(-))") (class "Default")
      (node (ref "DAC2") (pin "15") (pinfunction "VREF(-)_15") (pintype "power_in"))
      (node (ref "R11") (pin "2") (pinfunction "2_2") (pintype "passive"))
      (node (ref "R54") (pin "2") (pinfunction "2_2") (pintype "passive"))
    )
    (net (code "57") (name "Net-(DZ2-Pad2)") (class "Default")
      (node (ref "DZ2") (pin "2") (pinfunction "2_2") (pintype "passive"))
      (node (ref "FREQ") (pin "5") (pinfunction "5_5") (pintype "passive"))
      (node (ref "R23") (pin "2") (pinfunction "2_2") (pintype "passive"))
      (node (ref "R28") (pin "2") (pinfunction "2_2") (pintype "passive"))
    )
    (net (code "58") (name "Net-(DZ3-Pad2)") (class "Default")
      (node (ref "DZ3") (pin "2") (pinfunction "2_2") (pintype "passive"))
      (node (ref "FREQ") (pin "2") (pinfunction "2_2") (pintype "passive"))
      (node (ref "R20") (pin "2") (pinfunction "2_2") (pintype "passive"))
      (node (ref "R29") (pin "2") (pinfunction "2_2") (pintype "passive"))
    )
    (net (code "59") (name "Net-(DZ4-Pad2)") (class "Default")
      (node (ref "DZ4") (pin "2") (pinfunction "2_2") (pintype "passive"))
      (node (ref "FREQ") (pin "6") (pinfunction "6_6") (pintype "passive"))
      (node (ref "R24") (pin "2") (pinfunction "2_2") (pintype "passive"))
      (node (ref "R30") (pin "2") (pinfunction "2_2") (pintype "passive"))
    )
    (net (code "60") (name "Net-(DZ5-Pad2)") (class "Default")
      (node (ref "DZ5") (pin "2") (pinfunction "2_2") (pintype "passive"))
      (node (ref "FREQ") (pin "3") (pinfunction "3_3") (pintype "passive"))
      (node (ref "R21") (pin "2") (pinfunction "2_2") (pintype "passive"))
      (node (ref "R31") (pin "2") (pinfunction "2_2") (pintype "passive"))
    )
    (net (code "61") (name "Net-(DZ6-Pad2)") (class "Default")
      (node (ref "DZ6") (pin "2") (pinfunction "2_2") (pintype "passive"))
      (node (ref "FREQ") (pin "7") (pinfunction "7_7") (pintype "passive"))
      (node (ref "R25") (pin "2") (pinfunction "2_2") (pintype "passive"))
      (node (ref "R32") (pin "2") (pinfunction "2_2") (pintype "passive"))
    )
    (net (code "62") (name "Net-(DZ7-Pad2)") (class "Default")
      (node (ref "DZ7") (pin "2") (pinfunction "2_2") (pintype "passive"))
      (node (ref "FREQ") (pin "4") (pinfunction "4_4") (pintype "passive"))
      (node (ref "R22") (pin "2") (pinfunction "2_2") (pintype "passive"))
      (node (ref "R33") (pin "2") (pinfunction "2_2") (pintype "passive"))
    )
    (net (code "63") (name "Net-(DZ8-Pad2)") (class "Default")
      (node (ref "DZ8") (pin "2") (pinfunction "2_2") (pintype "passive"))
      (node (ref "FREQ") (pin "1") (pinfunction "1_1") (pintype "passive"))
      (node (ref "R19") (pin "2") (pinfunction "2_2") (pintype "passive"))
      (node (ref "R27") (pin "2") (pinfunction "2_2") (pintype "passive"))
    )
    (net (code "64") (name "Net-(DZ9-Pad2)") (class "Default")
      (node (ref "DZ9") (pin "2") (pinfunction "2_2") (pintype "passive"))
      (node (ref "FREQ") (pin "8") (pinfunction "8_8") (pintype "passive"))
      (node (ref "R26") (pin "2") (pinfunction "2_2") (pintype "passive"))
      (node (ref "R34") (pin "2") (pinfunction "2_2") (pintype "passive"))
    )
    (net (code "65") (name "Net-(DZ12-Pad2)") (class "Default")
      (node (ref "DZ12") (pin "2") (pinfunction "2_2") (pintype "passive"))
      (node (ref "FPGA") (pin "3") (pinfunction "3_3") (pintype "passive"))
      (node (ref "R37") (pin "1") (pinfunction "1_1") (pintype "passive"))
      (node (ref "R38") (pin "2") (pinfunction "2_2") (pintype "passive"))
    )
    (net (code "66") (name "Net-(DZ13-Pad2)") (class "Default")
      (node (ref "DZ13") (pin "2") (pinfunction "2_2") (pintype "passive"))
      (node (ref "FPGA") (pin "5") (pinfunction "5_5") (pintype "passive"))
      (node (ref "R42") (pin "2") (pinfunction "2_2") (pintype "passive"))
      (node (ref "R43") (pin "2") (pinfunction "2_2") (pintype "passive"))
    )
    (net (code "67") (name "Net-(DZ14-Pad2)") (class "Default")
      (node (ref "DZ14") (pin "2") (pinfunction "2_2") (pintype "passive"))
      (node (ref "FPGA") (pin "1") (pinfunction "1_1") (pintype "passive"))
      (node (ref "R50") (pin "1") (pinfunction "1_1") (pintype "passive"))
      (node (ref "R51") (pin "2") (pinfunction "2_2") (pintype "passive"))
    )
    (net (code "68") (name "Net-(FPGA-Pad4)") (class "Default")
      (node (ref "FPGA") (pin "4") (pinfunction "4_4") (pintype "passive"))
      (node (ref "J5") (pin "2") (pinfunction "2_2") (pintype "passive"))
    )
    (net (code "69") (name "Net-(FPGA-Pad9)") (class "Default")
      (node (ref "FPGA") (pin "9") (pinfunction "9_9") (pintype "passive"))
      (node (ref "R41") (pin "2") (pinfunction "2_2") (pintype "passive"))
    )
    (net (code "70") (name "Net-(IO-Pad1)") (class "Default")
      (node (ref "IO") (pin "1") (pinfunction "1_1") (pintype "passive"))
      (node (ref "R44") (pin "1") (pinfunction "1_1") (pintype "passive"))
    )
    (net (code "71") (name "Net-(IO-Pad2)") (class "Default")
      (node (ref "IO") (pin "2") (pinfunction "2_2") (pintype "passive"))
      (node (ref "PUENTE_FR") (pin "2") (pinfunction "2_2") (pintype "passive"))
    )
    (net (code "72") (name "Net-(R2-Pad2)") (class "Default")
      (node (ref "R2") (pin "2") (pinfunction "2_2") (pintype "passive"))
      (node (ref "R3") (pin "1") (pinfunction "1_1") (pintype "passive"))
    )
    (net (code "73") (name "Net-(R12-Pad2)") (class "Default")
      (node (ref "R12") (pin "2") (pinfunction "2_2") (pintype "passive"))
      (node (ref "R13") (pin "1") (pinfunction "1_1") (pintype "passive"))
    )
    (net (code "74") (name "Net-(R19-Pad1)") (class "Default")
      (node (ref "R19") (pin "1") (pinfunction "1_1") (pintype "passive"))
      (node (ref "S3.") (pin "16") (pinfunction "16_16") (pintype "passive"))
    )
    (net (code "75") (name "Net-(R20-Pad1)") (class "Default")
      (node (ref "R20") (pin "1") (pinfunction "1_1") (pintype "passive"))
      (node (ref "S3.") (pin "15") (pinfunction "15_15") (pintype "passive"))
    )
    (net (code "76") (name "Net-(R21-Pad1)") (class "Default")
      (node (ref "R21") (pin "1") (pinfunction "1_1") (pintype "passive"))
      (node (ref "S3.") (pin "14") (pinfunction "14_14") (pintype "passive"))
    )
    (net (code "77") (name "Net-(R22-Pad1)") (class "Default")
      (node (ref "R22") (pin "1") (pinfunction "1_1") (pintype "passive"))
      (node (ref "S3.") (pin "13") (pinfunction "13_13") (pintype "passive"))
    )
    (net (code "78") (name "Net-(R23-Pad1)") (class "Default")
      (node (ref "R23") (pin "1") (pinfunction "1_1") (pintype "passive"))
      (node (ref "S3.") (pin "12") (pinfunction "12_12") (pintype "passive"))
    )
    (net (code "79") (name "Net-(R24-Pad1)") (class "Default")
      (node (ref "R24") (pin "1") (pinfunction "1_1") (pintype "passive"))
      (node (ref "S3.") (pin "11") (pinfunction "11_11") (pintype "passive"))
    )
    (net (code "80") (name "Net-(R25-Pad1)") (class "Default")
      (node (ref "R25") (pin "1") (pinfunction "1_1") (pintype "passive"))
      (node (ref "S3.") (pin "10") (pinfunction "10_10") (pintype "passive"))
    )
    (net (code "81") (name "Net-(R26-Pad1)") (class "Default")
      (node (ref "R26") (pin "1") (pinfunction "1_1") (pintype "passive"))
      (node (ref "S3.") (pin "9") (pinfunction "9_9") (pintype "passive"))
    )
    (net (code "82") (name "Net-(R40-Pad1)") (class "Default")
      (node (ref "R40") (pin "1") (pinfunction "1_1") (pintype "passive"))
      (node (ref "SCHMITT") (pin "2") (pinfunction "2_2") (pintype "passive"))
    )
    (net (code "83") (name "Net-(S/H-CH)") (class "Default")
      (node (ref "C8") (pin "1") (pinfunction "1_1") (pintype "passive"))
      (node (ref "S/H") (pin "6") (pinfunction "CH_6") (pintype "passive"))
    )
    (net (code "84") (name "Net-(T1-B)") (class "Default")
      (node (ref "R17") (pin "1") (pinfunction "1_1") (pintype "passive"))
      (node (ref "T1") (pin "1") (pinfunction "B_1") (pintype "passive"))
    )
    (net (code "85") (name "Net-(T2-B)") (class "Default")
      (node (ref "R46") (pin "1") (pinfunction "1_1") (pintype "passive"))
      (node (ref "T2") (pin "1") (pinfunction "B_1") (pintype "passive"))
    )
    (net (code "86") (name "Net-(T2-C)") (class "Default")
      (node (ref "R47") (pin "2") (pinfunction "2_2") (pintype "passive"))
      (node (ref "T2") (pin "2") (pinfunction "C_2") (pintype "passive"))
      (node (ref "U5") (pin "1") (pinfunction "CLK_1") (pintype "input"))
      (node (ref "U6") (pin "1") (pinfunction "CLK_1") (pintype "input"))
    )
    (net (code "87") (name "Net-(T3-B)") (class "Default")
      (node (ref "R49") (pin "2") (pinfunction "2_2") (pintype "passive"))
      (node (ref "T3") (pin "1") (pinfunction "B_1") (pintype "passive"))
    )
    (net (code "88") (name "Net-(T3-E)") (class "Default")
      (node (ref "FPGA") (pin "2") (pinfunction "2_2") (pintype "passive"))
      (node (ref "T3") (pin "3") (pinfunction "E_3") (pintype "passive"))
    )
    (net (code "89") (name "Net-(T4-B)") (class "Default")
      (node (ref "R52") (pin "2") (pinfunction "2_2") (pintype "passive"))
      (node (ref "T4") (pin "1") (pinfunction "B_1") (pintype "passive"))
    )
    (net (code "90") (name "Net-(U1A-Y1)") (class "Default")
      (node (ref "D1") (pin "1") (pinfunction "1_1") (pintype "passive"))
      (node (ref "U1") (pin "18") (pinfunction "Y1_18") (pintype "tri_state"))
    )
    (net (code "91") (name "Net-(U1A-Y2)") (class "Default")
      (node (ref "D2") (pin "1") (pinfunction "1_1") (pintype "passive"))
      (node (ref "U1") (pin "16") (pinfunction "Y2_16") (pintype "tri_state"))
    )
    (net (code "92") (name "Net-(U1A-Y3)") (class "Default")
      (node (ref "D3") (pin "1") (pinfunction "1_1") (pintype "passive"))
      (node (ref "U1") (pin "14") (pinfunction "Y3_14") (pintype "tri_state"))
    )
    (net (code "93") (name "Net-(U1A-Y4)") (class "Default")
      (node (ref "D4") (pin "1") (pinfunction "1_1") (pintype "passive"))
      (node (ref "U1") (pin "12") (pinfunction "Y4_12") (pintype "tri_state"))
    )
    (net (code "94") (name "Net-(U1B-Y1)") (class "Default")
      (node (ref "D5") (pin "1") (pinfunction "1_1") (pintype "passive"))
      (node (ref "U1") (pin "9") (pinfunction "Y1_9") (pintype "tri_state"))
    )
    (net (code "95") (name "Net-(U1B-Y2)") (class "Default")
      (node (ref "D6") (pin "1") (pinfunction "1_1") (pintype "passive"))
      (node (ref "U1") (pin "7") (pinfunction "Y2_7") (pintype "tri_state"))
    )
    (net (code "96") (name "Net-(U1B-Y3)") (class "Default")
      (node (ref "D7") (pin "1") (pinfunction "1_1") (pintype "passive"))
      (node (ref "U1") (pin "5") (pinfunction "Y3_5") (pintype "tri_state"))
    )
    (net (code "97") (name "Net-(U1B-Y4)") (class "Default")
      (node (ref "D8") (pin "1") (pinfunction "1_1") (pintype "passive"))
      (node (ref "U1") (pin "3") (pinfunction "Y4_3") (pintype "tri_state"))
    )
    (net (code "98") (name "Net-(U2-Q0)") (class "Default")
      (node (ref "OUT_LATCHED") (pin "1") (pinfunction "1_1") (pintype "passive"))
      (node (ref "S1") (pin "1") (pinfunction "1_1") (pintype "passive"))
      (node (ref "U2") (pin "2") (pinfunction "Q0_2") (pintype "tri_state"))
    )
    (net (code "99") (name "Net-(U2-Q1)") (class "Default")
      (node (ref "OUT_LATCHED") (pin "2") (pinfunction "2_2") (pintype "passive"))
      (node (ref "S1") (pin "2") (pinfunction "2_2") (pintype "passive"))
      (node (ref "U2") (pin "5") (pinfunction "Q1_5") (pintype "tri_state"))
    )
    (net (code "100") (name "Net-(U2-Q2)") (class "Default")
      (node (ref "OUT_LATCHED") (pin "3") (pinfunction "3_3") (pintype "passive"))
      (node (ref "S1") (pin "3") (pinfunction "3_3") (pintype "passive"))
      (node (ref "U2") (pin "6") (pinfunction "Q2_6") (pintype "tri_state"))
    )
    (net (code "101") (name "Net-(U2-Q3)") (class "Default")
      (node (ref "OUT_LATCHED") (pin "4") (pinfunction "4_4") (pintype "passive"))
      (node (ref "S1") (pin "4") (pinfunction "4_4") (pintype "passive"))
      (node (ref "U2") (pin "9") (pinfunction "Q3_9") (pintype "tri_state"))
    )
    (net (code "102") (name "Net-(U2-Q4)") (class "Default")
      (node (ref "OUT_LATCHED") (pin "5") (pinfunction "5_5") (pintype "passive"))
      (node (ref "S1") (pin "5") (pinfunction "5_5") (pintype "passive"))
      (node (ref "U2") (pin "12") (pinfunction "Q4_12") (pintype "tri_state"))
    )
    (net (code "103") (name "Net-(U2-Q5)") (class "Default")
      (node (ref "OUT_LATCHED") (pin "6") (pinfunction "6_6") (pintype "passive"))
      (node (ref "S1") (pin "6") (pinfunction "6_6") (pintype "passive"))
      (node (ref "U2") (pin "15") (pinfunction "Q5_15") (pintype "tri_state"))
    )
    (net (code "104") (name "Net-(U2-Q6)") (class "Default")
      (node (ref "OUT_LATCHED") (pin "7") (pinfunction "7_7") (pintype "passive"))
      (node (ref "S1") (pin "7") (pinfunction "7_7") (pintype "passive"))
      (node (ref "U2") (pin "16") (pinfunction "Q6_16") (pintype "tri_state"))
    )
    (net (code "105") (name "Net-(U2-Q7)") (class "Default")
      (node (ref "OUT_LATCHED") (pin "8") (pinfunction "8_8") (pintype "passive"))
      (node (ref "S1") (pin "8") (pinfunction "8_8") (pintype "passive"))
      (node (ref "U2") (pin "19") (pinfunction "Q7_19") (pintype "tri_state"))
    )
    (net (code "106") (name "Net-(U5-OPIN-)") (class "Default")
      (node (ref "U5") (pin "3") (pinfunction "OPOUT_3") (pintype "output"))
      (node (ref "U5") (pin "4") (pinfunction "OPIN-_4") (pintype "input"))
    )
    (net (code "107") (name "Net-(U5-OUT)") (class "Default")
      (node (ref "PUENTE_FR") (pin "3") (pinfunction "3_3") (pintype "passive"))
      (node (ref "U5") (pin "5") (pinfunction "OUT_5") (pintype "output"))
    )
    (net (code "108") (name "Net-(U6-IN)") (class "Default")
      (node (ref "D11") (pin "1") (pinfunction "1_1") (pintype "passive"))
      (node (ref "D9") (pin "2") (pinfunction "2_2") (pintype "passive"))
      (node (ref "PUENTE_FAA") (pin "3") (pinfunction "3_3") (pintype "passive"))
      (node (ref "R1") (pin "2") (pinfunction "2_2") (pintype "passive"))
      (node (ref "U6") (pin "8") (pinfunction "IN_8") (pintype "input"))
      (node (ref "U8") (pin "7") (pinfunction "OUT_7") (pintype "output"))
    )
    (net (code "109") (name "Net-(U6-OPIN-)") (class "Default")
      (node (ref "U6") (pin "3") (pinfunction "OPOUT_3") (pintype "output"))
      (node (ref "U6") (pin "4") (pinfunction "OPIN-_4") (pintype "input"))
    )
    (net (code "110") (name "Net-(U6-OUT)") (class "Default")
      (node (ref "FOUT") (pin "1") (pinfunction "1_1") (pintype "passive"))
      (node (ref "PUENTE_FAA") (pin "1") (pinfunction "1_1") (pintype "passive"))
      (node (ref "U6") (pin "5") (pinfunction "OUT_5") (pintype "output"))
    )
    (net (code "111") (name "Net-(U8A-IN+)") (class "Default")
      (node (ref "R14") (pin "1") (pinfunction "1_1") (pintype "passive"))
      (node (ref "R16") (pin "1") (pinfunction "1_1") (pintype "passive"))
      (node (ref "U8") (pin "3") (pinfunction "IN+_3") (pintype "input"))
    )
    (net (code "112") (name "Net-(U8A-IN-)") (class "Default")
      (node (ref "R15") (pin "1") (pinfunction "1_1") (pintype "passive"))
      (node (ref "U8") (pin "1") (pinfunction "OUT_1") (pintype "output"))
      (node (ref "U8") (pin "2") (pinfunction "IN-_2") (pintype "input"))
    )
    (net (code "113") (name "Net-(U8B-IN+)") (class "Default")
      (node (ref "R44") (pin "2") (pinfunction "2_2") (pintype "passive"))
      (node (ref "R45") (pin "1") (pinfunction "1_1") (pintype "passive"))
      (node (ref "U8") (pin "5") (pinfunction "IN+_5") (pintype "input"))
    )
    (net (code "114") (name "Net-(U8B-IN-)") (class "Default")
      (node (ref "R1") (pin "1") (pinfunction "1_1") (pintype "passive"))
      (node (ref "R15") (pin "2") (pinfunction "2_2") (pintype "passive"))
      (node (ref "U8") (pin "6") (pinfunction "IN-_6") (pintype "input"))
    )
    (net (code "115") (name "VCC_3.3") (class "Default")
      (node (ref "C18") (pin "1") (pinfunction "1_1") (pintype "passive"))
      (node (ref "J5") (pin "3") (pinfunction "3_3") (pintype "passive"))
      (node (ref "R17") (pin "2") (pinfunction "2_2") (pintype "passive"))
      (node (ref "R41") (pin "3") (pinfunction "3_3") (pintype "passive"))
      (node (ref "R46") (pin "2") (pinfunction "2_2") (pintype "passive"))
      (node (ref "R49") (pin "1") (pinfunction "1_1") (pintype "passive"))
      (node (ref "R52") (pin "1") (pinfunction "1_1") (pintype "passive"))
      (node (ref "R6") (pin "2") (pinfunction "2_2") (pintype "passive"))
      (node (ref "S3.") (pin "1") (pinfunction "1_1") (pintype "passive"))
      (node (ref "S3.") (pin "2") (pinfunction "2_2") (pintype "passive"))
      (node (ref "S3.") (pin "3") (pinfunction "3_3") (pintype "passive"))
      (node (ref "S3.") (pin "4") (pinfunction "4_4") (pintype "passive"))
      (node (ref "S3.") (pin "5") (pinfunction "5_5") (pintype "passive"))
      (node (ref "S3.") (pin "6") (pinfunction "6_6") (pintype "passive"))
      (node (ref "S3.") (pin "7") (pinfunction "7_7") (pintype "passive"))
      (node (ref "S3.") (pin "8") (pinfunction "8_8") (pintype "passive"))
      (node (ref "U4") (pin "3") (pinfunction "VOut_3") (pintype "passive"))
    )
    (net (code "116") (name "VCC_5") (class "Default")
      (node (ref "ADC") (pin "11") (pinfunction "VCC_11") (pintype "power_in"))
      (node (ref "ADC") (pin "12") (pinfunction "VREF(+)_12") (pintype "passive"))
      (node (ref "C14") (pin "1") (pinfunction "1_1") (pintype "passive"))
      (node (ref "C16") (pin "1") (pinfunction "1_1") (pintype "passive"))
      (node (ref "C17") (pin "2") (pinfunction "2_2") (pintype "passive"))
      (node (ref "C24") (pin "1") (pinfunction "1_1") (pintype "passive"))
      (node (ref "C25") (pin "2") (pinfunction "2_2") (pintype "passive"))
      (node (ref "C26") (pin "1") (pinfunction "1_1") (pintype "passive"))
      (node (ref "D11") (pin "2") (pinfunction "2_2") (pintype "passive"))
      (node (ref "D12") (pin "2") (pinfunction "2_2") (pintype "passive"))
      (node (ref "D13") (pin "2") (pinfunction "2_2") (pintype "passive"))
      (node (ref "DZ10") (pin "2") (pinfunction "2_2") (pintype "passive"))
      (node (ref "FPGA_ALIM") (pin "1") (pinfunction "1_1") (pintype "passive"))
      (node (ref "OE") (pin "2") (pinfunction "2_2") (pintype "passive"))
      (node (ref "R18") (pin "2") (pinfunction "2_2") (pintype "passive"))
      (node (ref "R35") (pin "2") (pinfunction "2_2") (pintype "passive"))
      (node (ref "R47") (pin "1") (pinfunction "1_1") (pintype "passive"))
      (node (ref "R48") (pin "1") (pinfunction "1_1") (pintype "passive"))
      (node (ref "R53") (pin "1") (pinfunction "1_1") (pintype "passive"))
      (node (ref "U1") (pin "20") (pinfunction "VDD_20") (pintype "power_in"))
      (node (ref "U2") (pin "20") (pinfunction "VDD_20") (pintype "power_in"))
      (node (ref "U3") (pin "3") (pinfunction "VOut_3") (pintype "passive"))
      (node (ref "U5") (pin "7") (pinfunction "V+_7") (pintype "power_in"))
      (node (ref "U6") (pin "7") (pinfunction "V+_7") (pintype "power_in"))
    )
    (net (code "117") (name "VCC_10") (class "Default")
      (node (ref "ALIMENTACION") (pin "3") (pinfunction "3_3") (pintype "passive"))
      (node (ref "C1") (pin "1") (pinfunction "1_1") (pintype "passive"))
      (node (ref "C11") (pin "2") (pinfunction "2_2") (pintype "passive"))
      (node (ref "C13") (pin "1") (pinfunction "1_1") (pintype "passive"))
      (node (ref "C15") (pin "1") (pinfunction "1_1") (pintype "passive"))
      (node (ref "C3") (pin "2") (pinfunction "2_2") (pintype "passive"))
      (node (ref "C5") (pin "1") (pinfunction "1_1") (pintype "passive"))
      (node (ref "C7") (pin "1") (pinfunction "1_1") (pintype "passive"))
      (node (ref "C9") (pin "1") (pinfunction "1_1") (pintype "passive"))
      (node (ref "COMP") (pin "8") (pinfunction "V+_8") (pintype "power_in"))
      (node (ref "DAC1") (pin "13") (pinfunction "V+_13") (pintype "power_in"))
      (node (ref "DAC2") (pin "13") (pinfunction "V+_13") (pintype "power_in"))
      (node (ref "R10") (pin "1") (pinfunction "1_1") (pintype "passive"))
      (node (ref "R4") (pin "2") (pinfunction "2_2") (pintype "passive"))
      (node (ref "R55") (pin "1") (pinfunction "1_1") (pintype "passive"))
      (node (ref "R57") (pin "2") (pinfunction "2_2") (pintype "passive"))
      (node (ref "S/H") (pin "4") (pinfunction "V-_4") (pintype "power_in"))
      (node (ref "TRANSIMPEDANCIA") (pin "8") (pinfunction "V+_8") (pintype "power_in"))
      (node (ref "U3") (pin "1") (pinfunction "VIn_1") (pintype "passive"))
      (node (ref "U4") (pin "1") (pinfunction "VIn_1") (pintype "passive"))
      (node (ref "U8") (pin "8") (pinfunction "V+_8") (pintype "power_in"))
    )
    (net (code "118") (name "VEE_5") (class "Default")
      (node (ref "C19") (pin "1") (pinfunction "1_1") (pintype "passive"))
      (node (ref "C20") (pin "1") (pinfunction "1_1") (pintype "passive"))
      (node (ref "C23") (pin "1") (pinfunction "1_1") (pintype "passive"))
      (node (ref "D14") (pin "1") (pinfunction "1_1") (pintype "passive"))
      (node (ref "DZ11") (pin "1") (pinfunction "1_1") (pintype "passive"))
      (node (ref "R14") (pin "2") (pinfunction "2_2") (pintype "passive"))
      (node (ref "R14") (pin "3") (pinfunction "3_3") (pintype "passive"))
      (node (ref "R36") (pin "2") (pinfunction "2_2") (pintype "passive"))
      (node (ref "U5") (pin "2") (pinfunction "V-_2") (pintype "power_in"))
      (node (ref "U6") (pin "2") (pinfunction "V-_2") (pintype "power_in"))
      (node (ref "U7") (pin "3") (pinfunction "VOut_3") (pintype "passive"))
    )
    (net (code "119") (name "VEE_10") (class "Default")
      (node (ref "ALIMENTACION") (pin "1") (pinfunction "1_1") (pintype "passive"))
      (node (ref "C10") (pin "2") (pinfunction "2_2") (pintype "passive"))
      (node (ref "C12") (pin "2") (pinfunction "2_2") (pintype "passive"))
      (node (ref "C2") (pin "2") (pinfunction "2_2") (pintype "passive"))
      (node (ref "C21") (pin "1") (pinfunction "1_1") (pintype "passive"))
      (node (ref "C22") (pin "2") (pinfunction "2_2") (pintype "passive"))
      (node (ref "C4") (pin "1") (pinfunction "1_1") (pintype "passive"))
      (node (ref "C6") (pin "1") (pinfunction "1_1") (pintype "passive"))
      (node (ref "DAC1") (pin "3") (pinfunction "V-_3") (pintype "power_in"))
      (node (ref "DAC2") (pin "3") (pinfunction "V-_3") (pintype "power_in"))
      (node (ref "S/H") (pin "1") (pinfunction "V+_1") (pintype "power_in"))
      (node (ref "U7") (pin "2") (pinfunction "VIn_2") (pintype "passive"))
      (node (ref "U8") (pin "4") (pinfunction "V-_4") (pintype "power_in"))
    )
    (net (code "120") (name "unconnected-(COMP-BAL-Pad5)") (class "Default")
      (node (ref "COMP") (pin "5") (pinfunction "BAL_5") (pintype "passive+no_connect"))
    )
    (net (code "121") (name "unconnected-(COMP-BAL{slash}STB-Pad6)") (class "Default")
      (node (ref "COMP") (pin "6") (pinfunction "BAL/STB_6") (pintype "passive+no_connect"))
    )
    (net (code "122") (name "unconnected-(S/H-OFFSET_ADJ-Pad2)") (class "Default")
      (node (ref "S/H") (pin "2") (pinfunction "OFFSET_ADJ_2") (pintype "input+no_connect"))
    )
    (net (code "123") (name "unconnected-(TRANSIMPEDANCIAB-GND-Pad4)") (class "Default")
      (node (ref "TRANSIMPEDANCIA") (pin "4") (pinfunction "GND_4") (pintype "power_in+no_connect"))
    )
    (net (code "124") (name "unconnected-(TRANSIMPEDANCIAB-V+-Pad8)") (class "Default")
      (node (ref "TRANSIMPEDANCIA") (pin "8") (pinfunction "V+_8") (pintype "power_in+no_connect"))
    )
    (net (code "125") (name "unconnected-(U8B-V+-Pad8)") (class "Default")
      (node (ref "U8") (pin "8") (pinfunction "V+_8") (pintype "power_in+no_connect"))
    )
    (net (code "126") (name "unconnected-(U8B-V--Pad4)") (class "Default")
      (node (ref "U8") (pin "4") (pinfunction "V-_4") (pintype "power_in+no_connect"))
    )
  )
)
